# bontor_mbed_lowpan_rev_b.net
KiCad netlist of a schematic drawn in EAGLE
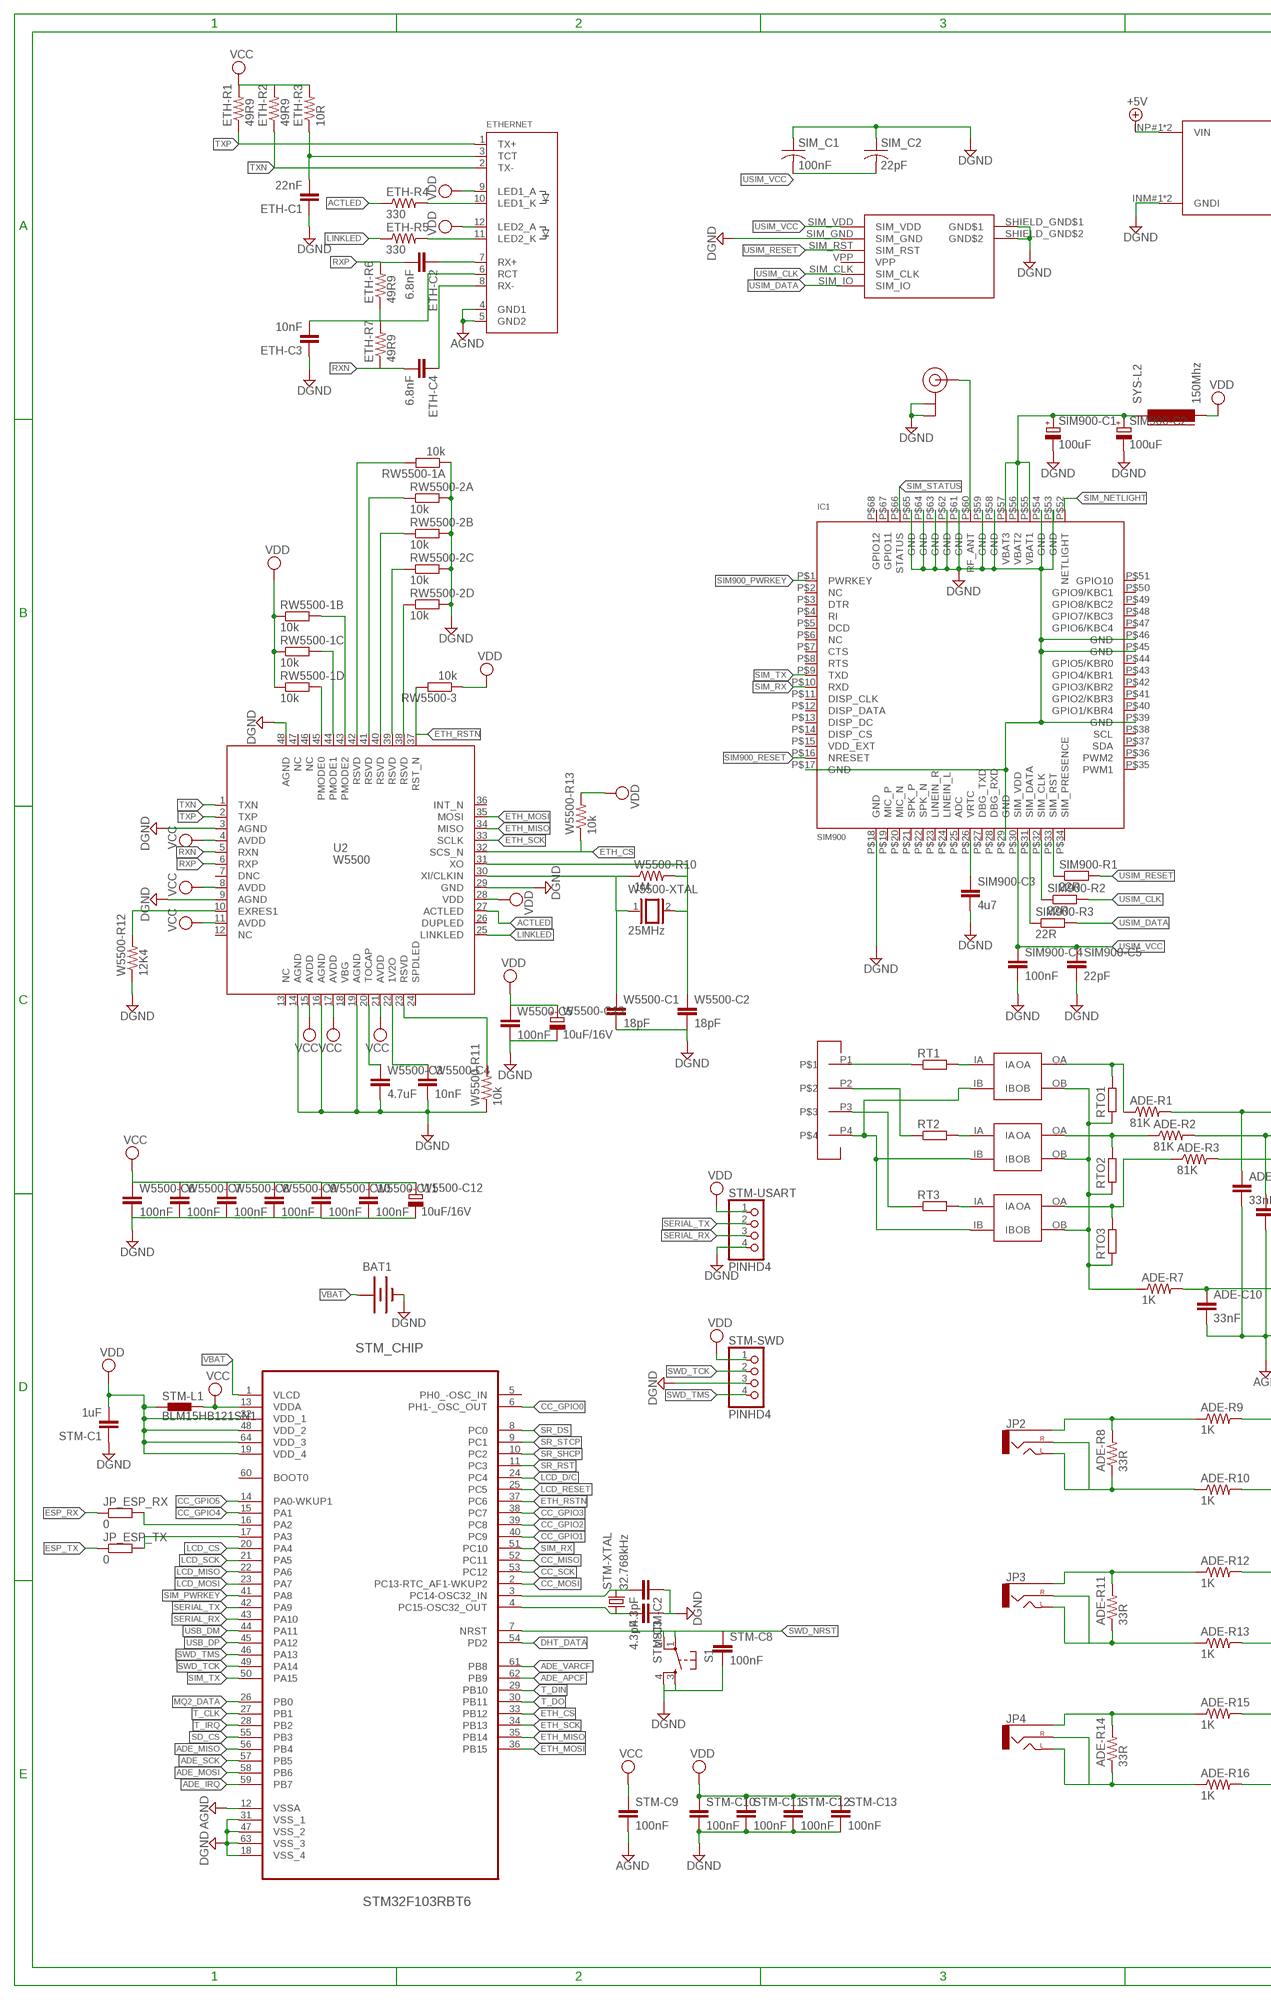
[diagram p0: schematic, sheet 1, part 1 of 2]
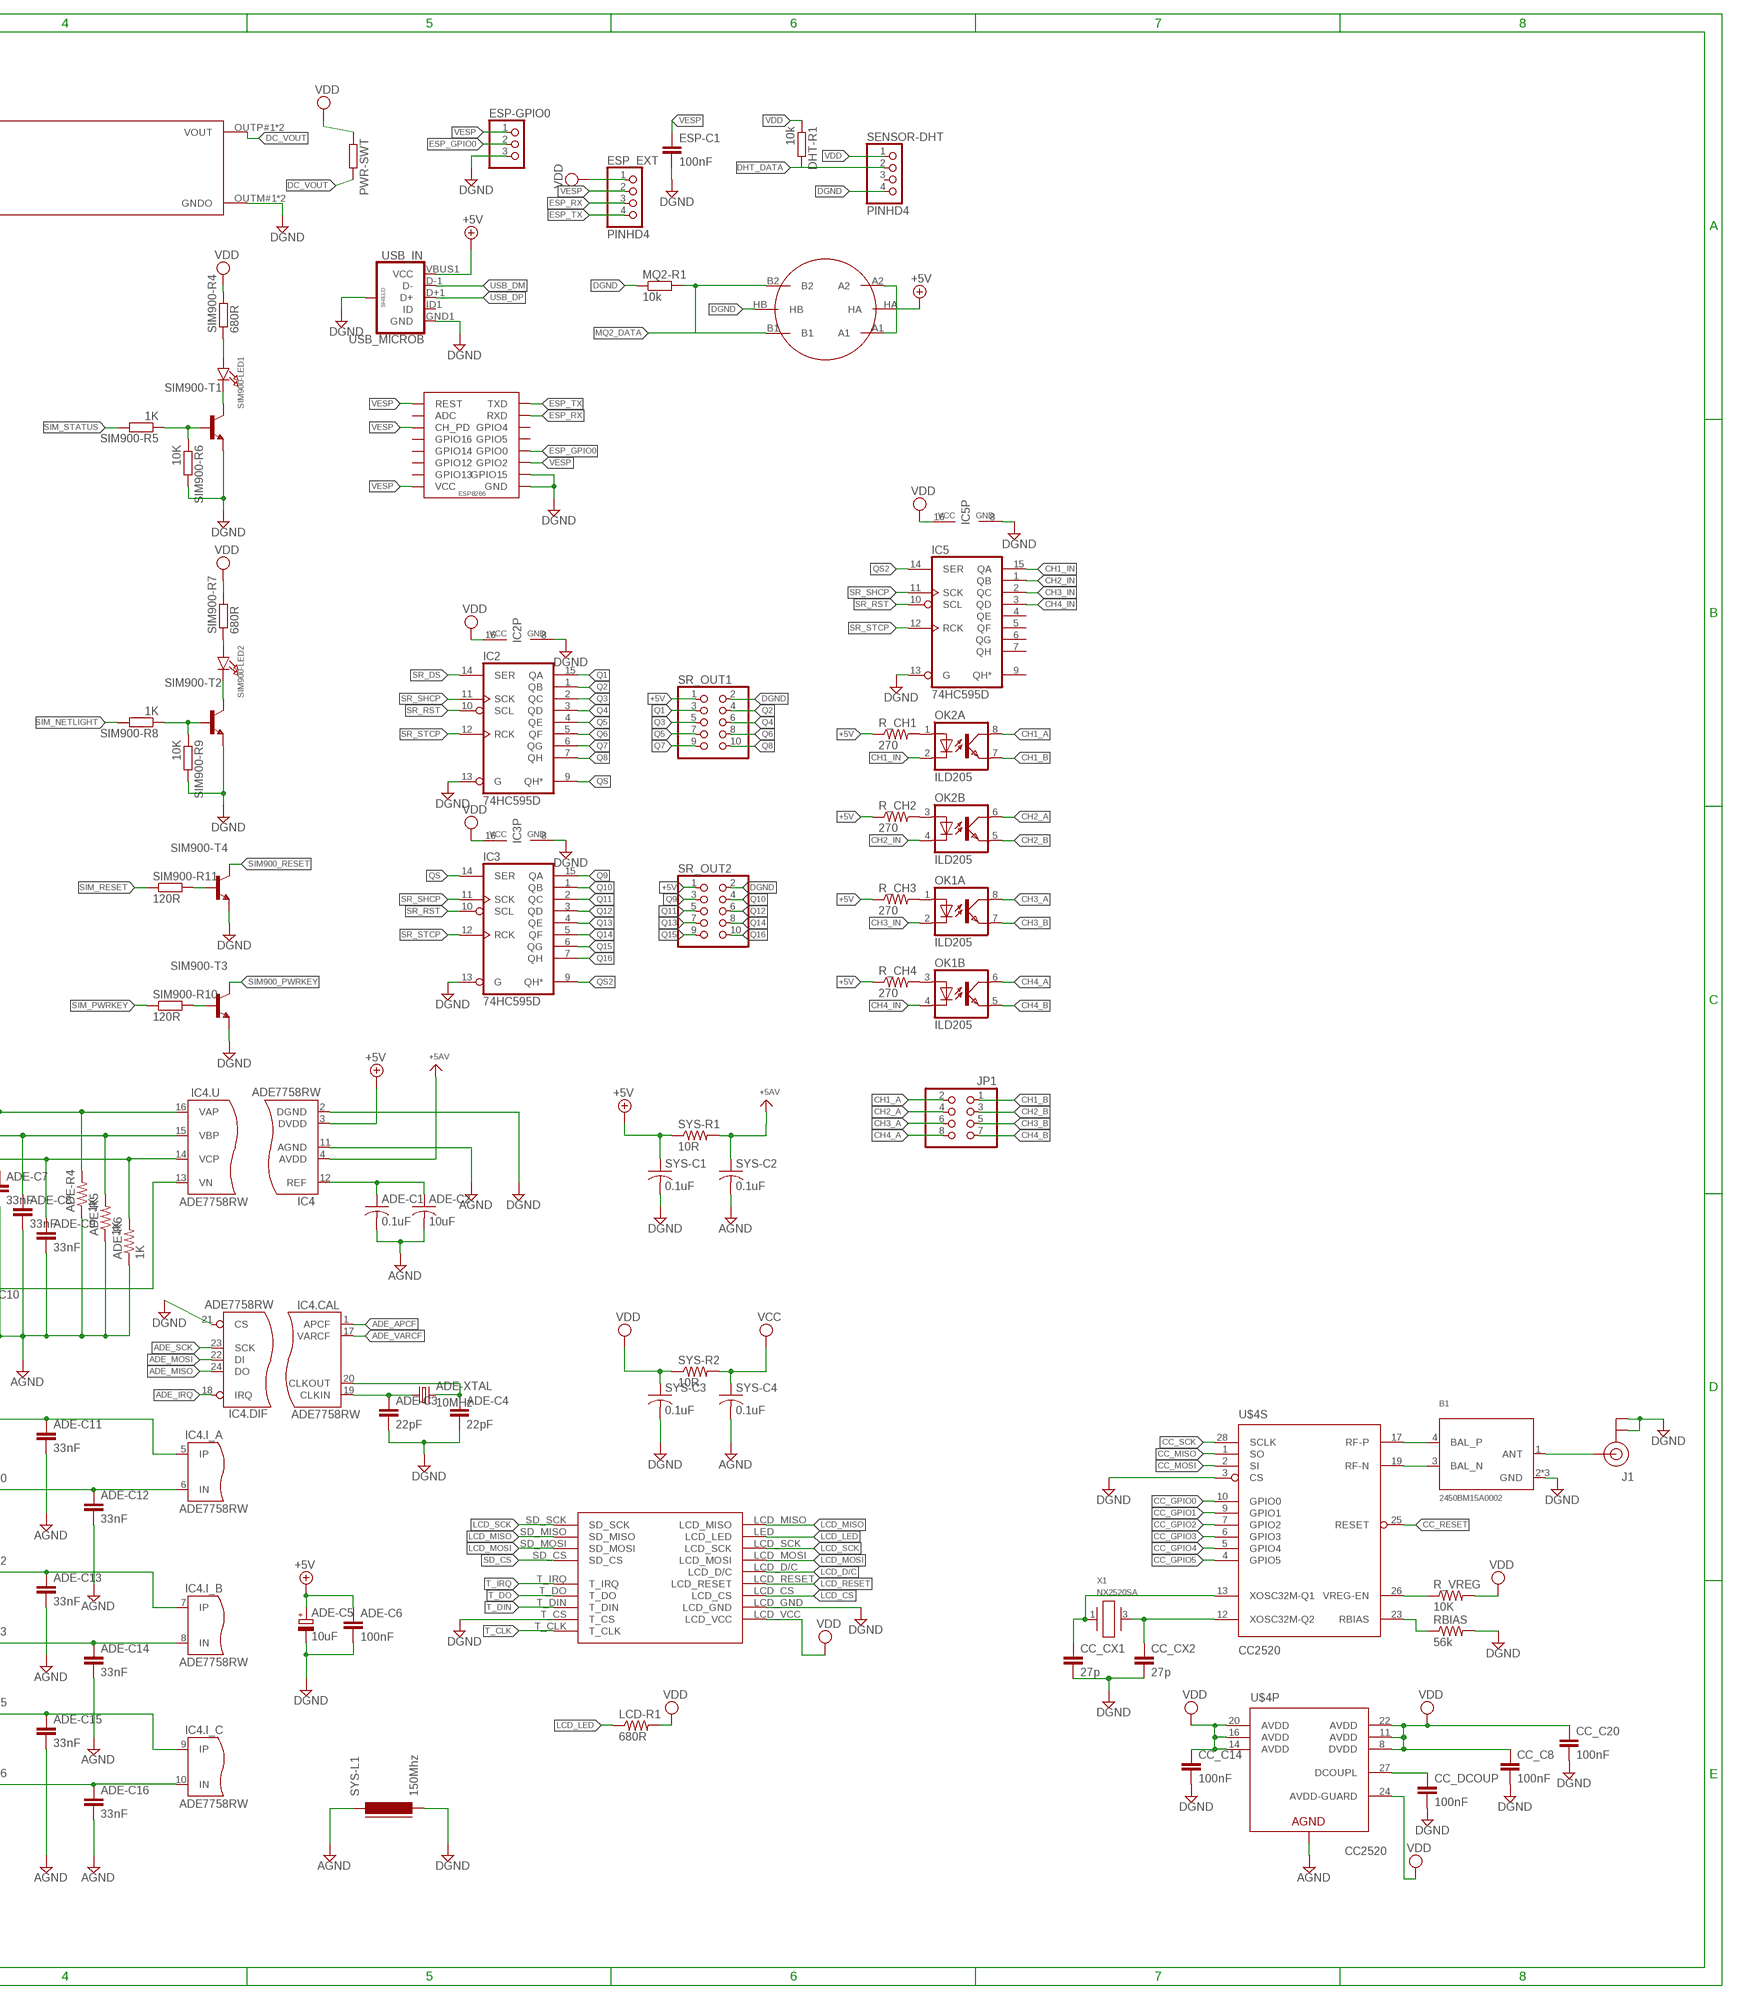
[diagram p1: schematic, sheet 1, part 2 of 2]

(export (version "E")
  (design (tool "Eeschema 10.0.6"))
  (components
    (comp (ref "ADE-C1")
      (value "0.1uF")
      (footprint "eagle-import:C0603@1")
      (libsource (lib "eagle-import") (part "C-USC0603"))
    )
    (comp (ref "ADE-C2")
      (value "10uF")
      (footprint "eagle-import:C0805K")
      (libsource (lib "eagle-import") (part "C-USC0805K"))
    )
    (comp (ref "ADE-C3")
      (value "22pF")
      (footprint "eagle-import:C0603")
      (libsource (lib "eagle-import") (part "C-EUC0603"))
    )
    (comp (ref "ADE-C4")
      (value "22pF")
      (footprint "eagle-import:C0603")
      (libsource (lib "eagle-import") (part "C-EUC0603"))
    )
    (comp (ref "ADE-C5")
      (value "10uF")
      (footprint "eagle-import:153CLV-0605")
      (libsource (lib "eagle-import") (part "CPOL-EU153CLV-0605"))
    )
    (comp (ref "ADE-C6")
      (value "100nF")
      (footprint "eagle-import:C0603")
      (libsource (lib "eagle-import") (part "C-EUC0603"))
    )
    (comp (ref "ADE-C7")
      (value "33nF")
      (footprint "eagle-import:0603-CAP")
      (libsource (lib "eagle-import") (part "CAP0603-CAP"))
    )
    (comp (ref "ADE-C8")
      (value "33nF")
      (footprint "eagle-import:0603-CAP")
      (libsource (lib "eagle-import") (part "CAP0603-CAP"))
    )
    (comp (ref "ADE-C9")
      (value "33nF")
      (footprint "eagle-import:0603-CAP")
      (libsource (lib "eagle-import") (part "CAP0603-CAP"))
    )
    (comp (ref "ADE-C10")
      (value "33nF")
      (footprint "eagle-import:0603-CAP")
      (libsource (lib "eagle-import") (part "CAP0603-CAP"))
    )
    (comp (ref "ADE-C11")
      (value "33nF")
      (footprint "eagle-import:0603-CAP")
      (libsource (lib "eagle-import") (part "CAP0603-CAP"))
    )
    (comp (ref "ADE-C12")
      (value "33nF")
      (footprint "eagle-import:0603-CAP")
      (libsource (lib "eagle-import") (part "CAP0603-CAP"))
    )
    (comp (ref "ADE-C13")
      (value "33nF")
      (footprint "eagle-import:0603-CAP")
      (libsource (lib "eagle-import") (part "CAP0603-CAP"))
    )
    (comp (ref "ADE-C14")
      (value "33nF")
      (footprint "eagle-import:0603-CAP")
      (libsource (lib "eagle-import") (part "CAP0603-CAP"))
    )
    (comp (ref "ADE-C15")
      (value "33nF")
      (footprint "eagle-import:0603-CAP")
      (libsource (lib "eagle-import") (part "CAP0603-CAP"))
    )
    (comp (ref "ADE-C16")
      (value "33nF")
      (footprint "eagle-import:0603-CAP")
      (libsource (lib "eagle-import") (part "CAP0603-CAP"))
    )
    (comp (ref "ADE-R1")
      (value "81K")
      (footprint "eagle-import:0603-RES")
      (libsource (lib "eagle-import") (part "RESISTOR0603-RES"))
    )
    (comp (ref "ADE-R2")
      (value "81K")
      (footprint "eagle-import:0603-RES")
      (libsource (lib "eagle-import") (part "RESISTOR0603-RES"))
    )
    (comp (ref "ADE-R3")
      (value "81K")
      (footprint "eagle-import:0603-RES")
      (libsource (lib "eagle-import") (part "RESISTOR0603-RES"))
    )
    (comp (ref "ADE-R4")
      (value "1K")
      (footprint "eagle-import:0603-RES")
      (libsource (lib "eagle-import") (part "RESISTOR0603-RES"))
    )
    (comp (ref "ADE-R5")
      (value "1K")
      (footprint "eagle-import:0603-RES")
      (libsource (lib "eagle-import") (part "RESISTOR0603-RES"))
    )
    (comp (ref "ADE-R6")
      (value "1K")
      (footprint "eagle-import:0603-RES")
      (libsource (lib "eagle-import") (part "RESISTOR0603-RES"))
    )
    (comp (ref "ADE-R7")
      (value "1K")
      (footprint "eagle-import:0603-RES")
      (libsource (lib "eagle-import") (part "RESISTOR0603-RES"))
    )
    (comp (ref "ADE-R8")
      (value "33R")
      (footprint "eagle-import:0603-RES")
      (libsource (lib "eagle-import") (part "RESISTOR0603-RES"))
    )
    (comp (ref "ADE-R9")
      (value "1K")
      (footprint "eagle-import:0603-RES")
      (libsource (lib "eagle-import") (part "RESISTOR0603-RES"))
    )
    (comp (ref "ADE-R10")
      (value "1K")
      (footprint "eagle-import:0603-RES")
      (libsource (lib "eagle-import") (part "RESISTOR0603-RES"))
    )
    (comp (ref "ADE-R11")
      (value "33R")
      (footprint "eagle-import:0603-RES")
      (libsource (lib "eagle-import") (part "RESISTOR0603-RES"))
    )
    (comp (ref "ADE-R12")
      (value "1K")
      (footprint "eagle-import:0603-RES")
      (libsource (lib "eagle-import") (part "RESISTOR0603-RES"))
    )
    (comp (ref "ADE-R13")
      (value "1K")
      (footprint "eagle-import:0603-RES")
      (libsource (lib "eagle-import") (part "RESISTOR0603-RES"))
    )
    (comp (ref "ADE-R14")
      (value "33R")
      (footprint "eagle-import:0603-RES")
      (libsource (lib "eagle-import") (part "RESISTOR0603-RES"))
    )
    (comp (ref "ADE-R15")
      (value "1K")
      (footprint "eagle-import:0603-RES")
      (libsource (lib "eagle-import") (part "RESISTOR0603-RES"))
    )
    (comp (ref "ADE-R16")
      (value "1K")
      (footprint "eagle-import:0603-RES")
      (libsource (lib "eagle-import") (part "RESISTOR0603-RES"))
    )
    (comp (ref "ADE-XTAL")
      (value "10MHz")
      (footprint "eagle-import:HC49US")
      (libsource (lib "eagle-import") (part "CRYSTALHC49US"))
    )
    (comp (ref "B1")
      (value "2450BM15A0002")
      (footprint "eagle-import:2450BM")
      (libsource (lib "eagle-import") (part "2450BM15A0002"))
    )
    (comp (ref "BAT1")
      (value "BATTERY12MM")
      (footprint "eagle-import:BATTCON_12MM")
      (libsource (lib "eagle-import") (part "BATTERY12MM"))
    )
    (comp (ref "CC_C8")
      (value "100nF")
      (footprint "eagle-import:C0402")
      (libsource (lib "eagle-import") (part "C-EUC0402"))
    )
    (comp (ref "CC_C14")
      (value "100nF")
      (footprint "eagle-import:C0402")
      (libsource (lib "eagle-import") (part "C-EUC0402"))
    )
    (comp (ref "CC_C20")
      (value "100nF")
      (footprint "eagle-import:C0402")
      (libsource (lib "eagle-import") (part "C-EUC0402"))
    )
    (comp (ref "CC_CX1")
      (value "27p")
      (footprint "eagle-import:C0201")
      (libsource (lib "eagle-import") (part "C-EUC0201"))
    )
    (comp (ref "CC_CX2")
      (value "27p")
      (footprint "eagle-import:C0201")
      (libsource (lib "eagle-import") (part "C-EUC0201"))
    )
    (comp (ref "CC_DCOUP")
      (value "100nF")
      (footprint "eagle-import:C0402")
      (libsource (lib "eagle-import") (part "C-EUC0402"))
    )
    (comp (ref "DCDC-3.5V")
      (value "DCDCMODULE_SMALL")
      (footprint "eagle-import:DCDCMODULE-SMALL")
      (libsource (lib "eagle-import") (part "DCDCMODULE_SMALL"))
    )
    (comp (ref "DHT-R1")
      (value "10k")
      (footprint "eagle-import:R0603")
      (libsource (lib "eagle-import") (part "resistor_R-EU_R0603"))
    )
    (comp (ref "ESP-C1")
      (value "100nF")
      (footprint "eagle-import:C0603")
      (libsource (lib "eagle-import") (part "C-EUC0603"))
    )
    (comp (ref "ESP-GPIO0")
      (value "PINHD-1X3")
      (footprint "eagle-import:1X03")
      (libsource (lib "eagle-import") (part "PINHD-1X3"))
    )
    (comp (ref "ESP_EXT")
      (value "PINHD4")
      (footprint "eagle-import:PINHD4")
      (libsource (lib "eagle-import") (part "PINHD4"))
    )
    (comp (ref "ETH-C1")
      (value "22nF")
      (footprint "eagle-import:C0603")
      (libsource (lib "eagle-import") (part "C-EUC0603"))
    )
    (comp (ref "ETH-C2")
      (value "6.8nF")
      (footprint "eagle-import:C0603")
      (libsource (lib "eagle-import") (part "C-EUC0603"))
    )
    (comp (ref "ETH-C3")
      (value "10nF")
      (footprint "eagle-import:C0603")
      (libsource (lib "eagle-import") (part "C-EUC0603"))
    )
    (comp (ref "ETH-C4")
      (value "6.8nF")
      (footprint "eagle-import:C0603")
      (libsource (lib "eagle-import") (part "C-EUC0603"))
    )
    (comp (ref "ETH-R1")
      (value "49R9")
      (footprint "eagle-import:R0603")
      (libsource (lib "eagle-import") (part "R-US_R0603"))
    )
    (comp (ref "ETH-R2")
      (value "49R9")
      (footprint "eagle-import:R0603")
      (libsource (lib "eagle-import") (part "R-US_R0603"))
    )
    (comp (ref "ETH-R3")
      (value "10R")
      (footprint "eagle-import:R0603")
      (libsource (lib "eagle-import") (part "R-US_R0603"))
    )
    (comp (ref "ETH-R4")
      (value "330")
      (footprint "eagle-import:R0603")
      (libsource (lib "eagle-import") (part "R-US_R0603"))
    )
    (comp (ref "ETH-R5")
      (value "330")
      (footprint "eagle-import:R0603")
      (libsource (lib "eagle-import") (part "R-US_R0603"))
    )
    (comp (ref "ETH-R6")
      (value "49R9")
      (footprint "eagle-import:R0603")
      (libsource (lib "eagle-import") (part "R-US_R0603"))
    )
    (comp (ref "ETH-R7")
      (value "49R9")
      (footprint "eagle-import:R0603")
      (libsource (lib "eagle-import") (part "R-US_R0603"))
    )
    (comp (ref "ETHERNET")
      (value "RJ45J0026D21BNL")
      (footprint "eagle-import:RJ45_PULSEJACK")
      (libsource (lib "eagle-import") (part "RJ45J0026D21BNL"))
    )
    (comp (ref "IC1")
      (value "SIM900")
      (footprint "eagle-import:SIM900_SMT")
      (libsource (lib "eagle-import") (part "GSM_SIM900_LITERAL"))
    )
    (comp (ref "IC2")
      (value "74HC595D")
      (footprint "eagle-import:SO16")
      (libsource (lib "eagle-import") (part "74595DHC"))
    )
    (comp (ref "IC3")
      (value "74HC595D")
      (footprint "eagle-import:SO16")
      (libsource (lib "eagle-import") (part "74595DHC"))
    )
    (comp (ref "IC4")
      (value "ADE7758RW")
      (footprint "eagle-import:SOIC24")
      (libsource (lib "eagle-import") (part "ADE7758RW"))
    )
    (comp (ref "IC5")
      (value "74HC595D")
      (footprint "eagle-import:SO16")
      (libsource (lib "eagle-import") (part "74595DHC"))
    )
    (comp (ref "J1")
      (value "U.FL")
      (footprint "eagle-import:U.FL")
      (libsource (lib "eagle-import") (part "SparkFun-Connectors_U.FL"))
    )
    (comp (ref "JP1")
      (value "PINHD-2X4")
      (footprint "eagle-import:2X04")
      (libsource (lib "eagle-import") (part "PINHD-2X4"))
    )
    (comp (ref "JP2")
      (value "AUDIO-JACKSMD2")
      (footprint "eagle-import:AUDIO-JACK-3.5MM-SMD")
      (libsource (lib "eagle-import") (part "AUDIO-JACKSMD2"))
    )
    (comp (ref "JP3")
      (value "AUDIO-JACKSMD2")
      (footprint "eagle-import:AUDIO-JACK-3.5MM-SMD")
      (libsource (lib "eagle-import") (part "AUDIO-JACKSMD2"))
    )
    (comp (ref "JP4")
      (value "AUDIO-JACKSMD2")
      (footprint "eagle-import:AUDIO-JACK-3.5MM-SMD")
      (libsource (lib "eagle-import") (part "AUDIO-JACKSMD2"))
    )
    (comp (ref "JP_ESP_RX")
      (value "0")
      (footprint "eagle-import:R0201")
      (libsource (lib "eagle-import") (part "R-EU_R0201"))
    )
    (comp (ref "JP_ESP_TX")
      (value "0")
      (footprint "eagle-import:R0201")
      (libsource (lib "eagle-import") (part "R-EU_R0201"))
    )
    (comp (ref "LCD-R1")
      (value "680R")
      (footprint "eagle-import:0603-RES")
      (libsource (lib "eagle-import") (part "RESISTOR0603-RES"))
    )
    (comp (ref "MQ2-R1")
      (value "10k")
      (footprint "eagle-import:R0603")
      (libsource (lib "eagle-import") (part "resistor_R-EU_R0603"))
    )
    (comp (ref "OK1")
      (value "ILD205")
      (footprint "eagle-import:SOIC08")
      (fields (field (name "MF") "VISHAY/TELEFUNKEN") (field (name "MPN") "ILD205T"))
      (libsource (lib "eagle-import") (part "ILD205"))
    )
    (comp (ref "OK2")
      (value "ILD205")
      (footprint "eagle-import:SOIC08")
      (fields (field (name "MF") "VISHAY/TELEFUNKEN") (field (name "MPN") "ILD205T"))
      (libsource (lib "eagle-import") (part "ILD205"))
    )
    (comp (ref "PWR-SWT")
      (value "R-EU_R0402")
      (footprint "eagle-import:R0402")
      (libsource (lib "eagle-import") (part "R-EU_R0402"))
    )
    (comp (ref "RBIAS")
      (value "56k")
      (footprint "eagle-import:0402-RES")
      (libsource (lib "eagle-import") (part "RESISTOR0402-RES"))
    )
    (comp (ref "RT1")
      (value "R-EU_0309/V")
      (footprint "eagle-import:0309V")
      (libsource (lib "eagle-import") (part "R-EU_0309/V"))
    )
    (comp (ref "RT2")
      (value "R-EU_0309/V")
      (footprint "eagle-import:0309V")
      (libsource (lib "eagle-import") (part "R-EU_0309/V"))
    )
    (comp (ref "RT3")
      (value "R-EU_0309/V")
      (footprint "eagle-import:0309V")
      (libsource (lib "eagle-import") (part "R-EU_0309/V"))
    )
    (comp (ref "RTO1")
      (value "R-EU_0309/12")
      (footprint "eagle-import:0309_12")
      (libsource (lib "eagle-import") (part "R-EU_0309/12"))
    )
    (comp (ref "RTO2")
      (value "R-EU_0309/12")
      (footprint "eagle-import:0309_12")
      (libsource (lib "eagle-import") (part "R-EU_0309/12"))
    )
    (comp (ref "RTO3")
      (value "R-EU_0309/12")
      (footprint "eagle-import:0309_12")
      (libsource (lib "eagle-import") (part "R-EU_0309/12"))
    )
    (comp (ref "RW5500-1")
      (value "10k")
      (footprint "eagle-import:RN8P-4R-CRA06S")
      (libsource (lib "eagle-import") (part "RESISTOR_ARRAY_4"))
    )
    (comp (ref "RW5500-2")
      (value "10k")
      (footprint "eagle-import:RN8P-4R-CRA06S")
      (libsource (lib "eagle-import") (part "RESISTOR_ARRAY_4"))
    )
    (comp (ref "RW5500-3")
      (value "10k")
      (footprint "eagle-import:R0603")
      (libsource (lib "eagle-import") (part "R-EU_R0603"))
    )
    (comp (ref "R_CH1")
      (value "270")
      (footprint "eagle-import:0603-RES")
      (libsource (lib "eagle-import") (part "RESISTOR0603-RES"))
    )
    (comp (ref "R_CH2")
      (value "270")
      (footprint "eagle-import:0603-RES")
      (libsource (lib "eagle-import") (part "RESISTOR0603-RES"))
    )
    (comp (ref "R_CH3")
      (value "270")
      (footprint "eagle-import:0603-RES")
      (libsource (lib "eagle-import") (part "RESISTOR0603-RES"))
    )
    (comp (ref "R_CH4")
      (value "270")
      (footprint "eagle-import:0603-RES")
      (libsource (lib "eagle-import") (part "RESISTOR0603-RES"))
    )
    (comp (ref "R_VREG")
      (value "10K")
      (footprint "eagle-import:0402-RES")
      (libsource (lib "eagle-import") (part "RESISTOR0402-RES"))
    )
    (comp (ref "S1")
      (value "TAC_SWITCHSMD")
      (footprint "eagle-import:TACTILE-SWITCH-SMD")
      (libsource (lib "eagle-import") (part "TAC_SWITCHSMD"))
    )
    (comp (ref "SENSOR-DHT")
      (value "PINHD4")
      (footprint "eagle-import:PINHD4")
      (libsource (lib "eagle-import") (part "PINHD4"))
    )
    (comp (ref "SENSOR-MQ2")
      (value "METHANE_SENSOR")
      (footprint "eagle-import:MQ-3")
      (libsource (lib "eagle-import") (part "METHANE_SENSOR"))
    )
    (comp (ref "SIM900-C1")
      (value "100uF")
      (footprint "eagle-import:153CLV-0605")
      (libsource (lib "eagle-import") (part "CPOL-EU153CLV-0605"))
    )
    (comp (ref "SIM900-C2")
      (value "100uF")
      (footprint "eagle-import:153CLV-0605")
      (libsource (lib "eagle-import") (part "CPOL-EU153CLV-0605"))
    )
    (comp (ref "SIM900-C3")
      (value "4u7")
      (footprint "eagle-import:C0603")
      (libsource (lib "eagle-import") (part "C-EUC0603"))
    )
    (comp (ref "SIM900-C4")
      (value "100nF")
      (footprint "eagle-import:C0603")
      (libsource (lib "eagle-import") (part "C-EUC0603"))
    )
    (comp (ref "SIM900-C5")
      (value "22pF")
      (footprint "eagle-import:C0603")
      (libsource (lib "eagle-import") (part "C-EUC0603"))
    )
    (comp (ref "SIM900-LED1")
      (value "LED0805_NOOUTLINE")
      (footprint "eagle-import:CHIPLED_0805_NOOUTLINE")
      (libsource (lib "eagle-import") (part "LED0805_NOOUTLINE"))
    )
    (comp (ref "SIM900-LED2")
      (value "LED0805_NOOUTLINE")
      (footprint "eagle-import:CHIPLED_0805_NOOUTLINE")
      (libsource (lib "eagle-import") (part "LED0805_NOOUTLINE"))
    )
    (comp (ref "SIM900-R1")
      (value "22R")
      (footprint "eagle-import:R0603")
      (libsource (lib "eagle-import") (part "R-EU_R0603"))
    )
    (comp (ref "SIM900-R2")
      (value "22R")
      (footprint "eagle-import:R0603")
      (libsource (lib "eagle-import") (part "R-EU_R0603"))
    )
    (comp (ref "SIM900-R3")
      (value "22R")
      (footprint "eagle-import:R0603")
      (libsource (lib "eagle-import") (part "R-EU_R0603"))
    )
    (comp (ref "SIM900-R4")
      (value "680R")
      (footprint "eagle-import:R0603")
      (libsource (lib "eagle-import") (part "R-EU_R0603"))
    )
    (comp (ref "SIM900-R5")
      (value "1K")
      (footprint "eagle-import:R0603")
      (libsource (lib "eagle-import") (part "R-EU_R0603"))
    )
    (comp (ref "SIM900-R6")
      (value "10K")
      (footprint "eagle-import:R0603")
      (libsource (lib "eagle-import") (part "R-EU_R0603"))
    )
    (comp (ref "SIM900-R7")
      (value "680R")
      (footprint "eagle-import:R0603")
      (libsource (lib "eagle-import") (part "R-EU_R0603"))
    )
    (comp (ref "SIM900-R8")
      (value "1K")
      (footprint "eagle-import:R0603")
      (libsource (lib "eagle-import") (part "R-EU_R0603"))
    )
    (comp (ref "SIM900-R9")
      (value "10K")
      (footprint "eagle-import:R0603")
      (libsource (lib "eagle-import") (part "R-EU_R0603"))
    )
    (comp (ref "SIM900-R10")
      (value "120R")
      (footprint "eagle-import:R0603")
      (libsource (lib "eagle-import") (part "resistor_R-EU_R0603"))
    )
    (comp (ref "SIM900-R11")
      (value "120R")
      (footprint "eagle-import:R0603")
      (libsource (lib "eagle-import") (part "resistor_R-EU_R0603"))
    )
    (comp (ref "SIM900-T1")
      (value "MMBT2222ALT1-NPN-SOT23-BEC")
      (footprint "eagle-import:SOT23-BEC")
      (libsource (lib "eagle-import") (part "-NPN-SOT23-BECMMBT2222ALT1"))
    )
    (comp (ref "SIM900-T2")
      (value "MMBT2222ALT1-NPN-SOT23-BEC")
      (footprint "eagle-import:SOT23-BEC")
      (libsource (lib "eagle-import") (part "-NPN-SOT23-BECMMBT2222ALT1"))
    )
    (comp (ref "SIM900-T3")
      (value "MMBT2222ALT1-NPN-SOT23-BEC")
      (footprint "eagle-import:SOT23-BEC")
      (libsource (lib "eagle-import") (part "transistor-neu-to92_-NPN-SOT23-BECMMBT2222ALT1"))
    )
    (comp (ref "SIM900-T4")
      (value "MMBT2222ALT1-NPN-SOT23-BEC")
      (footprint "eagle-import:SOT23-BEC")
      (libsource (lib "eagle-import") (part "transistor-neu-to92_-NPN-SOT23-BECMMBT2222ALT1"))
    )
    (comp (ref "SIM_C1")
      (value "100nF")
      (footprint "eagle-import:C0603K")
      (libsource (lib "eagle-import") (part "C-USC0603K"))
    )
    (comp (ref "SIM_C2")
      (value "22pF")
      (footprint "eagle-import:C0603K")
      (libsource (lib "eagle-import") (part "C-USC0603K"))
    )
    (comp (ref "SR_OUT1")
      (value "PINHD-2X5/90")
      (footprint "eagle-import:2X05_90")
      (libsource (lib "eagle-import") (part "PINHD-2X5/90"))
    )
    (comp (ref "SR_OUT2")
      (value "PINHD-2X5/90")
      (footprint "eagle-import:2X05_90")
      (libsource (lib "eagle-import") (part "PINHD-2X5/90"))
    )
    (comp (ref "STM-C1")
      (value "1uF")
      (footprint "eagle-import:C0603")
      (libsource (lib "eagle-import") (part "C-EUC0603"))
    )
    (comp (ref "STM-C2")
      (value "4.3pF")
      (footprint "eagle-import:C0603")
      (libsource (lib "eagle-import") (part "C-EUC0603"))
    )
    (comp (ref "STM-C3")
      (value "4.3pF")
      (footprint "eagle-import:C0603")
      (libsource (lib "eagle-import") (part "C-EUC0603"))
    )
    (comp (ref "STM-C8")
      (value "100nF")
      (footprint "eagle-import:C0603")
      (libsource (lib "eagle-import") (part "C-EUC0603"))
    )
    (comp (ref "STM-C9")
      (value "100nF")
      (footprint "eagle-import:C0603")
      (libsource (lib "eagle-import") (part "C-EUC0603"))
    )
    (comp (ref "STM-C10")
      (value "100nF")
      (footprint "eagle-import:C0603")
      (libsource (lib "eagle-import") (part "C-EUC0603"))
    )
    (comp (ref "STM-C11")
      (value "100nF")
      (footprint "eagle-import:C0603")
      (libsource (lib "eagle-import") (part "C-EUC0603"))
    )
    (comp (ref "STM-C12")
      (value "100nF")
      (footprint "eagle-import:C0603")
      (libsource (lib "eagle-import") (part "C-EUC0603"))
    )
    (comp (ref "STM-C13")
      (value "100nF")
      (footprint "eagle-import:C0603")
      (libsource (lib "eagle-import") (part "C-EUC0603"))
    )
    (comp (ref "STM-L1")
      (value "BLM15HB121SN1")
      (footprint "eagle-import:0402")
      (libsource (lib "eagle-import") (part "BLM15HB121SN1"))
    )
    (comp (ref "STM-SWD")
      (value "PINHD4")
      (footprint "eagle-import:PINHD4")
      (libsource (lib "eagle-import") (part "PINHD4"))
    )
    (comp (ref "STM-USART")
      (value "PINHD4")
      (footprint "eagle-import:PINHD4")
      (libsource (lib "eagle-import") (part "PINHD4"))
    )
    (comp (ref "STM-XTAL")
      (value "32.768kHz")
      (footprint "eagle-import:TC26H")
      (libsource (lib "eagle-import") (part "CRYSTALTC26H"))
    )
    (comp (ref "STM_CHIP")
      (value "STM32F103RBT6")
      (footprint "eagle-import:QFP50P1200X1200X160-64N")
      (fields (field (name "MPN") "STM32L152RBT6"))
      (libsource (lib "eagle-import") (part "STM32L152RBT6"))
    )
    (comp (ref "SYS-C1")
      (value "0.1uF")
      (footprint "eagle-import:C0603@1")
      (libsource (lib "eagle-import") (part "C-USC0603"))
    )
    (comp (ref "SYS-C2")
      (value "0.1uF")
      (footprint "eagle-import:C0603@1")
      (libsource (lib "eagle-import") (part "C-USC0603"))
    )
    (comp (ref "SYS-C3")
      (value "0.1uF")
      (footprint "eagle-import:C0603@1")
      (libsource (lib "eagle-import") (part "C-USC0603"))
    )
    (comp (ref "SYS-C4")
      (value "0.1uF")
      (footprint "eagle-import:C0603@1")
      (libsource (lib "eagle-import") (part "C-USC0603"))
    )
    (comp (ref "SYS-L1")
      (value "150Mhz")
      (footprint "eagle-import:FB805")
      (libsource (lib "eagle-import") (part "FERRITE-0805"))
    )
    (comp (ref "SYS-L2")
      (value "150Mhz")
      (footprint "eagle-import:FB805")
      (libsource (lib "eagle-import") (part "FERRITE-0805"))
    )
    (comp (ref "SYS-R1")
      (value "10R")
      (footprint "eagle-import:0603-RES")
      (libsource (lib "eagle-import") (part "RESISTOR0603-RES"))
    )
    (comp (ref "SYS-R2")
      (value "10R")
      (footprint "eagle-import:0603-RES")
      (libsource (lib "eagle-import") (part "RESISTOR0603-RES"))
    )
    (comp (ref "U$4")
      (value "CC2520")
      (footprint "eagle-import:QFN50P500X500X100-29N")
      (libsource (lib "eagle-import") (part "CC2520"))
    )
    (comp (ref "U$5")
      (value "ESP8266WI12")
      (footprint "eagle-import:WI12")
      (libsource (lib "eagle-import") (part "ESP8266WI12"))
    )
    (comp (ref "U$7")
      (value "U.FL")
      (footprint "eagle-import:U.FL")
      (libsource (lib "eagle-import") (part "U.FL"))
    )
    (comp (ref "U$8")
      (value "SIM_HOLDER")
      (footprint "eagle-import:SIMHOLDER-PUSHPUSH")
      (libsource (lib "eagle-import") (part "SIM_HOLDER"))
    )
    (comp (ref "U$9")
      (value "TRANSFORMER")
      (footprint "eagle-import:TV16")
      (libsource (lib "eagle-import") (part "TRANSFORMER"))
    )
    (comp (ref "U$10")
      (value "TRANSFORMER")
      (footprint "eagle-import:TV16")
      (libsource (lib "eagle-import") (part "TRANSFORMER"))
    )
    (comp (ref "U$11")
      (value "TRANSFORMER")
      (footprint "eagle-import:TV16")
      (libsource (lib "eagle-import") (part "TRANSFORMER"))
    )
    (comp (ref "U$12")
      (value "TERMINAL_BLOCK")
      (footprint "eagle-import:TERMINAL-RIGHT-ANGLE")
      (libsource (lib "eagle-import") (part "TERMINAL_BLOCK"))
    )
    (comp (ref "U$13")
      (value "LCD_2.4")
      (footprint "eagle-import:LCD_TOUCH_2-4")
      (libsource (lib "eagle-import") (part "LCD_2.4"))
    )
    (comp (ref "U2")
      (value "W5500")
      (footprint "eagle-import:W5500")
      (libsource (lib "eagle-import") (part "W5500"))
    )
    (comp (ref "USB_IN")
      (value "USB_MICROB")
      (footprint "eagle-import:USB-B-MICRO-SMD_V03")
      (libsource (lib "eagle-import") (part "USB_MICROB_PLUGCONN-11752"))
    )
    (comp (ref "W5500-C1")
      (value "18pF")
      (footprint "eagle-import:C0603")
      (libsource (lib "eagle-import") (part "C-EUC0603"))
    )
    (comp (ref "W5500-C2")
      (value "18pF")
      (footprint "eagle-import:C0603")
      (libsource (lib "eagle-import") (part "C-EUC0603"))
    )
    (comp (ref "W5500-C3")
      (value "4.7uF")
      (footprint "eagle-import:C0603")
      (libsource (lib "eagle-import") (part "C-EUC0603"))
    )
    (comp (ref "W5500-C4")
      (value "10nF")
      (footprint "eagle-import:C0603")
      (libsource (lib "eagle-import") (part "C-EUC0603"))
    )
    (comp (ref "W5500-C5")
      (value "100nF")
      (footprint "eagle-import:C0603")
      (libsource (lib "eagle-import") (part "C-EUC0603"))
    )
    (comp (ref "W5500-C6")
      (value "100nF")
      (footprint "eagle-import:C0603")
      (libsource (lib "eagle-import") (part "C-EUC0603"))
    )
    (comp (ref "W5500-C7")
      (value "100nF")
      (footprint "eagle-import:C0603")
      (libsource (lib "eagle-import") (part "C-EUC0603"))
    )
    (comp (ref "W5500-C8")
      (value "100nF")
      (footprint "eagle-import:C0603")
      (libsource (lib "eagle-import") (part "C-EUC0603"))
    )
    (comp (ref "W5500-C9")
      (value "100nF")
      (footprint "eagle-import:C0603")
      (libsource (lib "eagle-import") (part "C-EUC0603"))
    )
    (comp (ref "W5500-C10")
      (value "100nF")
      (footprint "eagle-import:C0603")
      (libsource (lib "eagle-import") (part "C-EUC0603"))
    )
    (comp (ref "W5500-C11")
      (value "100nF")
      (footprint "eagle-import:C0603")
      (libsource (lib "eagle-import") (part "C-EUC0603"))
    )
    (comp (ref "W5500-C12")
      (value "10uF/16V")
      (footprint "eagle-import:153CLV-0605")
      (libsource (lib "eagle-import") (part "CPOL-EU153CLV-0605"))
    )
    (comp (ref "W5500-C13")
      (value "10uF/16V")
      (footprint "eagle-import:153CLV-0605")
      (libsource (lib "eagle-import") (part "CPOL-EU153CLV-0605"))
    )
    (comp (ref "W5500-R10")
      (value "1M")
      (footprint "eagle-import:R0603")
      (libsource (lib "eagle-import") (part "R-US_R0603"))
    )
    (comp (ref "W5500-R11")
      (value "10k")
      (footprint "eagle-import:R0603")
      (libsource (lib "eagle-import") (part "R-US_R0603"))
    )
    (comp (ref "W5500-R12")
      (value "12K4")
      (footprint "eagle-import:R0805")
      (libsource (lib "eagle-import") (part "R-US_R0805"))
    )
    (comp (ref "W5500-R13")
      (value "10k")
      (footprint "eagle-import:R0603")
      (libsource (lib "eagle-import") (part "R-US_R0603"))
    )
    (comp (ref "W5500-XTAL")
      (value "25MHz")
      (footprint "eagle-import:QS")
      (libsource (lib "eagle-import") (part "XTAL/S"))
    )
    (comp (ref "X1")
      (value "NX2520SA")
      (footprint "eagle-import:NX2520SA")
      (libsource (lib "eagle-import") (part "NX2520SA"))
    )
  )
  (nets
    (net (code "1") (name "+5AV") (class "Default")
      (node (ref "IC4") (pin "4") (pinfunction "AVDD_4") (pintype "power_in"))
      (node (ref "SYS-C2") (pin "1") (pinfunction "1_1") (pintype "passive"))
      (node (ref "SYS-R1") (pin "2") (pinfunction "2_2") (pintype "passive"))
    )
    (net (code "2") (name "+5V") (class "Default")
      (node (ref "ADE-C5") (pin "+") (pinfunction "+_+") (pintype "passive"))
      (node (ref "ADE-C6") (pin "1") (pinfunction "1_1") (pintype "passive"))
      (node (ref "DCDC-3.5V") (pin "INP#1") (pinfunction "VIN_INP#1") (pintype "bidirectional"))
      (node (ref "DCDC-3.5V") (pin "INP#2") (pinfunction "VIN_INP#2") (pintype "bidirectional"))
      (node (ref "IC4") (pin "3") (pinfunction "DVDD_3") (pintype "power_in"))
      (node (ref "R_CH1") (pin "1") (pinfunction "1_1") (pintype "passive"))
      (node (ref "R_CH2") (pin "1") (pinfunction "1_1") (pintype "passive"))
      (node (ref "R_CH3") (pin "1") (pinfunction "1_1") (pintype "passive"))
      (node (ref "R_CH4") (pin "1") (pinfunction "1_1") (pintype "passive"))
      (node (ref "SENSOR-MQ2") (pin "A1") (pinfunction "A1_A1") (pintype "bidirectional"))
      (node (ref "SENSOR-MQ2") (pin "A2") (pinfunction "A2_A2") (pintype "bidirectional"))
      (node (ref "SENSOR-MQ2") (pin "HA") (pinfunction "HA_HA") (pintype "bidirectional"))
      (node (ref "SR_OUT1") (pin "1") (pinfunction "1_1") (pintype "passive"))
      (node (ref "SR_OUT2") (pin "1") (pinfunction "1_1") (pintype "passive"))
      (node (ref "SYS-C1") (pin "1") (pinfunction "1_1") (pintype "passive"))
      (node (ref "SYS-R1") (pin "1") (pinfunction "1_1") (pintype "passive"))
      (node (ref "USB_IN") (pin "VBUS1") (pinfunction "VCC_VBUS1") (pintype "bidirectional"))
    )
    (net (code "3") (name "/GPIO11") (class "Default")
      (node (ref "IC1") (pin "P$67") (pinfunction "GPIO11_P$67") (pintype "power_in"))
    )
    (net (code "4") (name "/GPIO12") (class "Default")
      (node (ref "IC1") (pin "P$68") (pinfunction "GPIO12_P$68") (pintype "power_in"))
    )
    (net (code "5") (name "ACTLED") (class "Default")
      (node (ref "ETH-R4") (pin "1") (pinfunction "1_1") (pintype "passive"))
      (node (ref "U2") (pin "27") (pinfunction "ACTLED_27") (pintype "passive"))
    )
    (net (code "6") (name "ADE_APCF") (class "Default")
      (node (ref "IC4") (pin "1") (pinfunction "APCF_1") (pintype "output"))
      (node (ref "STM_CHIP") (pin "62") (pinfunction "PB9_62") (pintype "bidirectional"))
    )
    (net (code "7") (name "ADE_IRQ") (class "Default")
      (node (ref "IC4") (pin "18") (pinfunction "IRQ_18") (pintype "output"))
      (node (ref "STM_CHIP") (pin "59") (pinfunction "PB7_59") (pintype "bidirectional"))
    )
    (net (code "8") (name "ADE_MISO") (class "Default")
      (node (ref "IC4") (pin "24") (pinfunction "DO_24") (pintype "output"))
      (node (ref "STM_CHIP") (pin "56") (pinfunction "PB4_56") (pintype "bidirectional"))
    )
    (net (code "9") (name "ADE_MOSI") (class "Default")
      (node (ref "IC4") (pin "22") (pinfunction "DI_22") (pintype "input"))
      (node (ref "STM_CHIP") (pin "58") (pinfunction "PB6_58") (pintype "bidirectional"))
    )
    (net (code "10") (name "ADE_SCK") (class "Default")
      (node (ref "IC4") (pin "23") (pinfunction "SCK_23") (pintype "input"))
      (node (ref "STM_CHIP") (pin "57") (pinfunction "PB5_57") (pintype "bidirectional"))
    )
    (net (code "11") (name "ADE_VARCF") (class "Default")
      (node (ref "IC4") (pin "17") (pinfunction "VARCF_17") (pintype "output"))
      (node (ref "STM_CHIP") (pin "61") (pinfunction "PB8_61") (pintype "bidirectional"))
    )
    (net (code "12") (name "AGND") (class "Default")
      (node (ref "ADE-C1") (pin "2") (pinfunction "2_2") (pintype "passive"))
      (node (ref "ADE-C10") (pin "2") (pinfunction "2_2") (pintype "passive"))
      (node (ref "ADE-C11") (pin "2") (pinfunction "2_2") (pintype "passive"))
      (node (ref "ADE-C12") (pin "2") (pinfunction "2_2") (pintype "passive"))
      (node (ref "ADE-C13") (pin "2") (pinfunction "2_2") (pintype "passive"))
      (node (ref "ADE-C14") (pin "2") (pinfunction "2_2") (pintype "passive"))
      (node (ref "ADE-C15") (pin "2") (pinfunction "2_2") (pintype "passive"))
      (node (ref "ADE-C16") (pin "2") (pinfunction "2_2") (pintype "passive"))
      (node (ref "ADE-C2") (pin "2") (pinfunction "2_2") (pintype "passive"))
      (node (ref "ADE-C7") (pin "2") (pinfunction "2_2") (pintype "passive"))
      (node (ref "ADE-C8") (pin "2") (pinfunction "2_2") (pintype "passive"))
      (node (ref "ADE-C9") (pin "2") (pinfunction "2_2") (pintype "passive"))
      (node (ref "ADE-R4") (pin "1") (pinfunction "1_1") (pintype "passive"))
      (node (ref "ADE-R5") (pin "1") (pinfunction "1_1") (pintype "passive"))
      (node (ref "ADE-R6") (pin "1") (pinfunction "1_1") (pintype "passive"))
      (node (ref "ETHERNET") (pin "4") (pinfunction "GND1_4") (pintype "bidirectional"))
      (node (ref "ETHERNET") (pin "5") (pinfunction "GND2_5") (pintype "bidirectional"))
      (node (ref "IC4") (pin "11") (pinfunction "AGND_11") (pintype "power_in"))
      (node (ref "STM-C9") (pin "2") (pinfunction "2_2") (pintype "passive"))
      (node (ref "STM_CHIP") (pin "12") (pinfunction "VSSA_12") (pintype "power_in"))
      (node (ref "SYS-C2") (pin "2") (pinfunction "2_2") (pintype "passive"))
      (node (ref "SYS-C4") (pin "2") (pinfunction "2_2") (pintype "passive"))
      (node (ref "SYS-L1") (pin "1") (pinfunction "1_1") (pintype "passive"))
      (node (ref "U$4") (pin "29") (pinfunction "AGND_29") (pintype "power_in"))
    )
    (net (code "13") (name "CC_GPIO0") (class "Default")
      (node (ref "STM_CHIP") (pin "6") (pinfunction "PH1-_OSC_OUT_6") (pintype "bidirectional"))
      (node (ref "U$4") (pin "10") (pinfunction "GPIO0_10") (pintype "output"))
    )
    (net (code "14") (name "CC_GPIO1") (class "Default")
      (node (ref "STM_CHIP") (pin "40") (pinfunction "PC9_40") (pintype "bidirectional"))
      (node (ref "U$4") (pin "9") (pinfunction "GPIO1_9") (pintype "output"))
    )
    (net (code "15") (name "CC_GPIO2") (class "Default")
      (node (ref "STM_CHIP") (pin "39") (pinfunction "PC8_39") (pintype "bidirectional"))
      (node (ref "U$4") (pin "7") (pinfunction "GPIO2_7") (pintype "bidirectional"))
    )
    (net (code "16") (name "CC_GPIO3") (class "Default")
      (node (ref "STM_CHIP") (pin "38") (pinfunction "PC7_38") (pintype "bidirectional"))
      (node (ref "U$4") (pin "6") (pinfunction "GPIO3_6") (pintype "bidirectional"))
    )
    (net (code "17") (name "CC_GPIO4") (class "Default")
      (node (ref "STM_CHIP") (pin "15") (pinfunction "PA1_15") (pintype "bidirectional"))
      (node (ref "U$4") (pin "5") (pinfunction "GPIO4_5") (pintype "bidirectional"))
    )
    (net (code "18") (name "CC_GPIO5") (class "Default")
      (node (ref "STM_CHIP") (pin "14") (pinfunction "PA0-WKUP1_14") (pintype "bidirectional"))
      (node (ref "U$4") (pin "4") (pinfunction "GPIO5_4") (pintype "bidirectional"))
    )
    (net (code "19") (name "CC_MISO") (class "Default")
      (node (ref "STM_CHIP") (pin "52") (pinfunction "PC11_52") (pintype "bidirectional"))
      (node (ref "U$4") (pin "1") (pinfunction "SO_1") (pintype "output"))
    )
    (net (code "20") (name "CC_MOSI") (class "Default")
      (node (ref "STM_CHIP") (pin "2") (pinfunction "PC13-RTC_AF1-WKUP2_2") (pintype "bidirectional"))
      (node (ref "U$4") (pin "2") (pinfunction "SI_2") (pintype "input"))
    )
    (net (code "21") (name "CC_RESET") (class "Default")
      (node (ref "U$4") (pin "25") (pinfunction "RESET_25") (pintype "input"))
    )
    (net (code "22") (name "CC_SCK") (class "Default")
      (node (ref "STM_CHIP") (pin "53") (pinfunction "PC12_53") (pintype "bidirectional"))
      (node (ref "U$4") (pin "28") (pinfunction "SCLK_28") (pintype "input"))
    )
    (net (code "23") (name "CH1_A") (class "Default")
      (node (ref "JP1") (pin "2") (pinfunction "2_2") (pintype "passive"))
      (node (ref "OK2") (pin "8") (pinfunction "COL_8") (pintype "passive"))
    )
    (net (code "24") (name "CH1_B") (class "Default")
      (node (ref "JP1") (pin "1") (pinfunction "1_1") (pintype "passive"))
      (node (ref "OK2") (pin "7") (pinfunction "EMIT_7") (pintype "passive"))
    )
    (net (code "25") (name "CH1_IN") (class "Default")
      (node (ref "IC5") (pin "15") (pinfunction "QA_15") (pintype "tri_state"))
      (node (ref "OK2") (pin "2") (pinfunction "C_2") (pintype "passive"))
    )
    (net (code "26") (name "CH2_A") (class "Default")
      (node (ref "JP1") (pin "4") (pinfunction "4_4") (pintype "passive"))
      (node (ref "OK2") (pin "6") (pinfunction "COL_6") (pintype "passive"))
    )
    (net (code "27") (name "CH2_B") (class "Default")
      (node (ref "JP1") (pin "3") (pinfunction "3_3") (pintype "passive"))
      (node (ref "OK2") (pin "5") (pinfunction "EMIT_5") (pintype "passive"))
    )
    (net (code "28") (name "CH2_IN") (class "Default")
      (node (ref "IC5") (pin "1") (pinfunction "QB_1") (pintype "tri_state"))
      (node (ref "OK2") (pin "4") (pinfunction "C_4") (pintype "passive"))
    )
    (net (code "29") (name "CH3_A") (class "Default")
      (node (ref "JP1") (pin "6") (pinfunction "6_6") (pintype "passive"))
      (node (ref "OK1") (pin "8") (pinfunction "COL_8") (pintype "passive"))
    )
    (net (code "30") (name "CH3_B") (class "Default")
      (node (ref "JP1") (pin "5") (pinfunction "5_5") (pintype "passive"))
      (node (ref "OK1") (pin "7") (pinfunction "EMIT_7") (pintype "passive"))
    )
    (net (code "31") (name "CH3_IN") (class "Default")
      (node (ref "IC5") (pin "2") (pinfunction "QC_2") (pintype "tri_state"))
      (node (ref "OK1") (pin "2") (pinfunction "C_2") (pintype "passive"))
    )
    (net (code "32") (name "CH4_A") (class "Default")
      (node (ref "JP1") (pin "8") (pinfunction "8_8") (pintype "passive"))
      (node (ref "OK1") (pin "6") (pinfunction "COL_6") (pintype "passive"))
    )
    (net (code "33") (name "CH4_B") (class "Default")
      (node (ref "JP1") (pin "7") (pinfunction "7_7") (pintype "passive"))
      (node (ref "OK1") (pin "5") (pinfunction "EMIT_5") (pintype "passive"))
    )
    (net (code "34") (name "CH4_IN") (class "Default")
      (node (ref "IC5") (pin "3") (pinfunction "QD_3") (pintype "tri_state"))
      (node (ref "OK1") (pin "4") (pinfunction "C_4") (pintype "passive"))
    )
    (net (code "35") (name "DC_VOUT") (class "Default")
      (node (ref "DCDC-3.5V") (pin "OUTP#1") (pinfunction "VOUT_OUTP#1") (pintype "bidirectional"))
      (node (ref "DCDC-3.5V") (pin "OUTP#2") (pinfunction "VOUT_OUTP#2") (pintype "bidirectional"))
      (node (ref "PWR-SWT") (pin "2") (pinfunction "2_2") (pintype "passive"))
    )
    (net (code "36") (name "DGND") (class "Default")
      (node (ref "ADE-C3") (pin "2") (pinfunction "2_2") (pintype "passive"))
      (node (ref "ADE-C4") (pin "2") (pinfunction "2_2") (pintype "passive"))
      (node (ref "ADE-C5") (pin "-") (pinfunction "-_-") (pintype "passive"))
      (node (ref "ADE-C6") (pin "2") (pinfunction "2_2") (pintype "passive"))
      (node (ref "B1") (pin "2") (pinfunction "GND_2") (pintype "bidirectional"))
      (node (ref "B1") (pin "5") (pinfunction "GND_5") (pintype "bidirectional"))
      (node (ref "B1") (pin "6") (pinfunction "GND_6") (pintype "bidirectional"))
      (node (ref "BAT1") (pin "GND") (pinfunction "-_GND") (pintype "power_in"))
      (node (ref "CC_C14") (pin "2") (pinfunction "2_2") (pintype "passive"))
      (node (ref "CC_C20") (pin "2") (pinfunction "2_2") (pintype "passive"))
      (node (ref "CC_C8") (pin "2") (pinfunction "2_2") (pintype "passive"))
      (node (ref "CC_CX1") (pin "2") (pinfunction "2_2") (pintype "passive"))
      (node (ref "CC_CX2") (pin "2") (pinfunction "2_2") (pintype "passive"))
      (node (ref "CC_DCOUP") (pin "2") (pinfunction "2_2") (pintype "passive"))
      (node (ref "DCDC-3.5V") (pin "INM#1") (pinfunction "GNDI_INM#1") (pintype "bidirectional"))
      (node (ref "DCDC-3.5V") (pin "INM#2") (pinfunction "GNDI_INM#2") (pintype "bidirectional"))
      (node (ref "DCDC-3.5V") (pin "OUTM#1") (pinfunction "GNDO_OUTM#1") (pintype "bidirectional"))
      (node (ref "DCDC-3.5V") (pin "OUTM#2") (pinfunction "GNDO_OUTM#2") (pintype "bidirectional"))
      (node (ref "ESP-C1") (pin "2") (pinfunction "2_2") (pintype "passive"))
      (node (ref "ESP-GPIO0") (pin "3") (pinfunction "3_3") (pintype "passive"))
      (node (ref "ETH-C1") (pin "1") (pinfunction "1_1") (pintype "passive"))
      (node (ref "ETH-C3") (pin "1") (pinfunction "1_1") (pintype "passive"))
      (node (ref "IC1") (pin "P$17") (pinfunction "GND_P$17") (pintype "power_in"))
      (node (ref "IC1") (pin "P$18") (pinfunction "GND_P$18") (pintype "power_in"))
      (node (ref "IC1") (pin "P$29") (pinfunction "GND_P$29") (pintype "power_in"))
      (node (ref "IC1") (pin "P$39") (pinfunction "GND_P$39") (pintype "power_in"))
      (node (ref "IC1") (pin "P$45") (pinfunction "GND_P$45") (pintype "power_in"))
      (node (ref "IC1") (pin "P$46") (pinfunction "GND_P$46") (pintype "power_in"))
      (node (ref "IC1") (pin "P$53") (pinfunction "GND_P$53") (pintype "power_in"))
      (node (ref "IC1") (pin "P$54") (pinfunction "GND_P$54") (pintype "power_in"))
      (node (ref "IC1") (pin "P$58") (pinfunction "GND_P$58") (pintype "power_in"))
      (node (ref "IC1") (pin "P$59") (pinfunction "GND_P$59") (pintype "power_in"))
      (node (ref "IC1") (pin "P$61") (pinfunction "GND_P$61") (pintype "power_in"))
      (node (ref "IC1") (pin "P$62") (pinfunction "GND_P$62") (pintype "power_in"))
      (node (ref "IC1") (pin "P$63") (pinfunction "GND_P$63") (pintype "power_in"))
      (node (ref "IC1") (pin "P$64") (pinfunction "GND_P$64") (pintype "power_in"))
      (node (ref "IC1") (pin "P$65") (pinfunction "GND_P$65") (pintype "power_in"))
      (node (ref "IC2") (pin "13") (pinfunction "G_13") (pintype "input"))
      (node (ref "IC2") (pin "8") (pinfunction "GND_8") (pintype "power_in"))
      (node (ref "IC3") (pin "13") (pinfunction "G_13") (pintype "input"))
      (node (ref "IC3") (pin "8") (pinfunction "GND_8") (pintype "power_in"))
      (node (ref "IC4") (pin "2") (pinfunction "DGND_2") (pintype "power_in"))
      (node (ref "IC4") (pin "21") (pinfunction "CS_21") (pintype "input"))
      (node (ref "IC5") (pin "13") (pinfunction "G_13") (pintype "input"))
      (node (ref "IC5") (pin "8") (pinfunction "GND_8") (pintype "power_in"))
      (node (ref "J1") (pin "P$1") (pinfunction "GND_P$1") (pintype "bidirectional"))
      (node (ref "J1") (pin "P$2") (pinfunction "GND_P$2") (pintype "bidirectional"))
      (node (ref "MQ2-R1") (pin "1") (pinfunction "1_1") (pintype "passive"))
      (node (ref "RBIAS") (pin "2") (pinfunction "2_2") (pintype "passive"))
      (node (ref "RW5500-1") (pin "1") (pinfunction "1_1") (pintype "passive"))
      (node (ref "RW5500-2") (pin "5") (pinfunction "2_5") (pintype "passive"))
      (node (ref "RW5500-2") (pin "6") (pinfunction "2_6") (pintype "passive"))
      (node (ref "RW5500-2") (pin "7") (pinfunction "2_7") (pintype "passive"))
      (node (ref "RW5500-2") (pin "8") (pinfunction "2_8") (pintype "passive"))
      (node (ref "S1") (pin "3") (pinfunction "3_3") (pintype "passive"))
      (node (ref "S1") (pin "4") (pinfunction "4_4") (pintype "passive"))
      (node (ref "SENSOR-DHT") (pin "4") (pinfunction "4_4") (pintype "passive"))
      (node (ref "SENSOR-MQ2") (pin "HB") (pinfunction "HB_HB") (pintype "bidirectional"))
      (node (ref "SIM900-C1") (pin "-") (pinfunction "-_-") (pintype "passive"))
      (node (ref "SIM900-C2") (pin "-") (pinfunction "-_-") (pintype "passive"))
      (node (ref "SIM900-C3") (pin "2") (pinfunction "2_2") (pintype "passive"))
      (node (ref "SIM900-C4") (pin "2") (pinfunction "2_2") (pintype "passive"))
      (node (ref "SIM900-C5") (pin "2") (pinfunction "2_2") (pintype "passive"))
      (node (ref "SIM900-R6") (pin "2") (pinfunction "2_2") (pintype "passive"))
      (node (ref "SIM900-R9") (pin "2") (pinfunction "2_2") (pintype "passive"))
      (node (ref "SIM900-T1") (pin "E") (pinfunction "E_E") (pintype "passive"))
      (node (ref "SIM900-T2") (pin "E") (pinfunction "E_E") (pintype "passive"))
      (node (ref "SIM900-T3") (pin "E") (pinfunction "E_E") (pintype "passive"))
      (node (ref "SIM900-T4") (pin "E") (pinfunction "E_E") (pintype "passive"))
      (node (ref "SIM_C1") (pin "1") (pinfunction "1_1") (pintype "passive"))
      (node (ref "SIM_C2") (pin "1") (pinfunction "1_1") (pintype "passive"))
      (node (ref "SR_OUT1") (pin "2") (pinfunction "2_2") (pintype "passive"))
      (node (ref "SR_OUT2") (pin "2") (pinfunction "2_2") (pintype "passive"))
      (node (ref "STM-C1") (pin "1") (pinfunction "1_1") (pintype "passive"))
      (node (ref "STM-C10") (pin "2") (pinfunction "2_2") (pintype "passive"))
      (node (ref "STM-C11") (pin "2") (pinfunction "2_2") (pintype "passive"))
      (node (ref "STM-C12") (pin "2") (pinfunction "2_2") (pintype "passive"))
      (node (ref "STM-C13") (pin "2") (pinfunction "2_2") (pintype "passive"))
      (node (ref "STM-C2") (pin "1") (pinfunction "1_1") (pintype "passive"))
      (node (ref "STM-C3") (pin "1") (pinfunction "1_1") (pintype "passive"))
      (node (ref "STM-C8") (pin "2") (pinfunction "2_2") (pintype "passive"))
      (node (ref "STM-SWD") (pin "3") (pinfunction "3_3") (pintype "passive"))
      (node (ref "STM-USART") (pin "4") (pinfunction "4_4") (pintype "passive"))
      (node (ref "STM_CHIP") (pin "18") (pinfunction "VSS_4_18") (pintype "power_in"))
      (node (ref "STM_CHIP") (pin "31") (pinfunction "VSS_1_31") (pintype "power_in"))
      (node (ref "STM_CHIP") (pin "47") (pinfunction "VSS_2_47") (pintype "power_in"))
      (node (ref "STM_CHIP") (pin "63") (pinfunction "VSS_3_63") (pintype "power_in"))
      (node (ref "SYS-C1") (pin "2") (pinfunction "2_2") (pintype "passive"))
      (node (ref "SYS-C3") (pin "2") (pinfunction "2_2") (pintype "passive"))
      (node (ref "SYS-L1") (pin "2") (pinfunction "2_2") (pintype "passive"))
      (node (ref "U$13") (pin "LCD_GND") (pinfunction "LCD_GND_LCD_GND") (pintype "power_in"))
      (node (ref "U$13") (pin "T_CS") (pinfunction "T_CS_T_CS") (pintype "bidirectional"))
      (node (ref "U$4") (pin "3") (pinfunction "CS_3") (pintype "input"))
      (node (ref "U$5") (pin "GND") (pinfunction "GND_GND") (pintype "bidirectional"))
      (node (ref "U$5") (pin "GPIO15") (pinfunction "GPIO15_GPIO15") (pintype "bidirectional"))
      (node (ref "U$7") (pin "P$1") (pinfunction "GND_P$1") (pintype "bidirectional"))
      (node (ref "U$7") (pin "P$2") (pinfunction "GND_P$2") (pintype "bidirectional"))
      (node (ref "U$8") (pin "SHIELD_GND$1") (pinfunction "GND$1_SHIELD_GND$1") (pintype "bidirectional"))
      (node (ref "U$8") (pin "SHIELD_GND$2") (pinfunction "GND$2_SHIELD_GND$2") (pintype "bidirectional"))
      (node (ref "U$8") (pin "SIM_GND") (pinfunction "SIM_GND_SIM_GND") (pintype "bidirectional"))
      (node (ref "U2") (pin "14") (pinfunction "AGND_14") (pintype "passive"))
      (node (ref "U2") (pin "16") (pinfunction "AGND_16") (pintype "passive"))
      (node (ref "U2") (pin "19") (pinfunction "AGND_19") (pintype "passive"))
      (node (ref "U2") (pin "29") (pinfunction "GND_29") (pintype "passive"))
      (node (ref "U2") (pin "3") (pinfunction "AGND_3") (pintype "passive"))
      (node (ref "U2") (pin "48") (pinfunction "AGND_48") (pintype "passive"))
      (node (ref "U2") (pin "9") (pinfunction "AGND_9") (pintype "passive"))
      (node (ref "USB_IN") (pin "GND1") (pinfunction "GND_GND1") (pintype "bidirectional"))
      (node (ref "USB_IN") (pin "SHIELD1") (pinfunction "SHIELD_SHIELD1") (pintype "bidirectional"))
      (node (ref "USB_IN") (pin "SHIELD2") (pinfunction "SHIELD_SHIELD2") (pintype "bidirectional"))
      (node (ref "USB_IN") (pin "SHIELD3") (pinfunction "SHIELD_SHIELD3") (pintype "bidirectional"))
      (node (ref "W5500-C1") (pin "2") (pinfunction "2_2") (pintype "passive"))
      (node (ref "W5500-C10") (pin "2") (pinfunction "2_2") (pintype "passive"))
      (node (ref "W5500-C11") (pin "2") (pinfunction "2_2") (pintype "passive"))
      (node (ref "W5500-C12") (pin "-") (pinfunction "-_-") (pintype "passive"))
      (node (ref "W5500-C13") (pin "-") (pinfunction "-_-") (pintype "passive"))
      (node (ref "W5500-C2") (pin "2") (pinfunction "2_2") (pintype "passive"))
      (node (ref "W5500-C3") (pin "2") (pinfunction "2_2") (pintype "passive"))
      (node (ref "W5500-C4") (pin "2") (pinfunction "2_2") (pintype "passive"))
      (node (ref "W5500-C5") (pin "2") (pinfunction "2_2") (pintype "passive"))
      (node (ref "W5500-C6") (pin "2") (pinfunction "2_2") (pintype "passive"))
      (node (ref "W5500-C7") (pin "2") (pinfunction "2_2") (pintype "passive"))
      (node (ref "W5500-C8") (pin "2") (pinfunction "2_2") (pintype "passive"))
      (node (ref "W5500-C9") (pin "2") (pinfunction "2_2") (pintype "passive"))
      (node (ref "W5500-R11") (pin "1") (pinfunction "1_1") (pintype "passive"))
      (node (ref "W5500-R12") (pin "1") (pinfunction "1_1") (pintype "passive"))
    )
    (net (code "37") (name "DHT_DATA") (class "Default")
      (node (ref "DHT-R1") (pin "2") (pinfunction "2_2") (pintype "passive"))
      (node (ref "SENSOR-DHT") (pin "2") (pinfunction "2_2") (pintype "passive"))
      (node (ref "STM_CHIP") (pin "54") (pinfunction "PD2_54") (pintype "bidirectional"))
    )
    (net (code "38") (name "ESP_GPIO0") (class "Default")
      (node (ref "ESP-GPIO0") (pin "2") (pinfunction "2_2") (pintype "passive"))
      (node (ref "U$5") (pin "GPIO00") (pinfunction "GPIO0_GPIO00") (pintype "bidirectional"))
    )
    (net (code "39") (name "ESP_RX") (class "Default")
      (node (ref "ESP_EXT") (pin "3") (pinfunction "3_3") (pintype "passive"))
      (node (ref "JP_ESP_RX") (pin "1") (pinfunction "1_1") (pintype "passive"))
      (node (ref "U$5") (pin "RXD") (pinfunction "RXD_RXD") (pintype "bidirectional"))
    )
    (net (code "40") (name "ESP_TX") (class "Default")
      (node (ref "ESP_EXT") (pin "4") (pinfunction "4_4") (pintype "passive"))
      (node (ref "JP_ESP_TX") (pin "1") (pinfunction "1_1") (pintype "passive"))
      (node (ref "U$5") (pin "TXD") (pinfunction "TXD_TXD") (pintype "bidirectional"))
    )
    (net (code "41") (name "ETH_CS") (class "Default")
      (node (ref "STM_CHIP") (pin "33") (pinfunction "PB12_33") (pintype "bidirectional"))
      (node (ref "U2") (pin "32") (pinfunction "SCS_N_32") (pintype "passive"))
      (node (ref "W5500-R13") (pin "1") (pinfunction "1_1") (pintype "passive"))
    )
    (net (code "42") (name "ETH_MISO") (class "Default")
      (node (ref "STM_CHIP") (pin "35") (pinfunction "PB14_35") (pintype "bidirectional"))
      (node (ref "U2") (pin "34") (pinfunction "MISO_34") (pintype "passive"))
    )
    (net (code "43") (name "ETH_MOSI") (class "Default")
      (node (ref "STM_CHIP") (pin "36") (pinfunction "PB15_36") (pintype "bidirectional"))
      (node (ref "U2") (pin "35") (pinfunction "MOSI_35") (pintype "passive"))
    )
    (net (code "44") (name "ETH_RSTN") (class "Default")
      (node (ref "RW5500-3") (pin "2") (pinfunction "2_2") (pintype "passive"))
      (node (ref "STM_CHIP") (pin "37") (pinfunction "PC6_37") (pintype "bidirectional"))
      (node (ref "U2") (pin "37") (pinfunction "RST_N_37") (pintype "passive"))
    )
    (net (code "45") (name "ETH_SCK") (class "Default")
      (node (ref "STM_CHIP") (pin "34") (pinfunction "PB13_34") (pintype "bidirectional"))
      (node (ref "U2") (pin "33") (pinfunction "SCLK_33") (pintype "passive"))
    )
    (net (code "46") (name "LCD_CS") (class "Default")
      (node (ref "STM_CHIP") (pin "20") (pinfunction "PA4_20") (pintype "bidirectional"))
      (node (ref "U$13") (pin "LCD_CS") (pinfunction "LCD_CS_LCD_CS") (pintype "bidirectional"))
    )
    (net (code "47") (name "LCD_D{slash}C") (class "Default")
      (node (ref "STM_CHIP") (pin "24") (pinfunction "PC4_24") (pintype "bidirectional"))
      (node (ref "U$13") (pin "LCD_D/C") (pinfunction "LCD_D/C_LCD_D/C") (pintype "bidirectional"))
    )
    (net (code "48") (name "LCD_LED") (class "Default")
      (node (ref "LCD-R1") (pin "1") (pinfunction "1_1") (pintype "passive"))
      (node (ref "U$13") (pin "LED") (pinfunction "LCD_LED_LED") (pintype "bidirectional"))
    )
    (net (code "49") (name "LCD_MISO") (class "Default")
      (node (ref "STM_CHIP") (pin "22") (pinfunction "PA6_22") (pintype "bidirectional"))
      (node (ref "U$13") (pin "LCD_MISO") (pinfunction "LCD_MISO_LCD_MISO") (pintype "bidirectional"))
      (node (ref "U$13") (pin "SD_MISO") (pinfunction "SD_MISO_SD_MISO") (pintype "bidirectional"))
    )
    (net (code "50") (name "LCD_MOSI") (class "Default")
      (node (ref "STM_CHIP") (pin "23") (pinfunction "PA7_23") (pintype "bidirectional"))
      (node (ref "U$13") (pin "LCD_MOSI") (pinfunction "LCD_MOSI_LCD_MOSI") (pintype "bidirectional"))
      (node (ref "U$13") (pin "SD_MOSI") (pinfunction "SD_MOSI_SD_MOSI") (pintype "bidirectional"))
    )
    (net (code "51") (name "LCD_RESET") (class "Default")
      (node (ref "STM_CHIP") (pin "25") (pinfunction "PC5_25") (pintype "bidirectional"))
      (node (ref "U$13") (pin "LCD_RESET") (pinfunction "LCD_RESET_LCD_RESET") (pintype "bidirectional"))
    )
    (net (code "52") (name "LCD_SCK") (class "Default")
      (node (ref "STM_CHIP") (pin "21") (pinfunction "PA5_21") (pintype "bidirectional"))
      (node (ref "U$13") (pin "LCD_SCK") (pinfunction "LCD_SCK_LCD_SCK") (pintype "bidirectional"))
      (node (ref "U$13") (pin "SD_SCK") (pinfunction "SD_SCK_SD_SCK") (pintype "bidirectional"))
    )
    (net (code "53") (name "LINKLED") (class "Default")
      (node (ref "ETH-R5") (pin "1") (pinfunction "1_1") (pintype "passive"))
      (node (ref "U2") (pin "25") (pinfunction "LINKLED_25") (pintype "passive"))
    )
    (net (code "54") (name "MQ2_DATA") (class "Default")
      (node (ref "MQ2-R1") (pin "2") (pinfunction "2_2") (pintype "passive"))
      (node (ref "SENSOR-MQ2") (pin "B1") (pinfunction "B1_B1") (pintype "bidirectional"))
      (node (ref "SENSOR-MQ2") (pin "B2") (pinfunction "B2_B2") (pintype "bidirectional"))
      (node (ref "STM_CHIP") (pin "26") (pinfunction "PB0_26") (pintype "bidirectional"))
    )
    (net (code "55") (name "Net-(ADE-R1-Pad1)") (class "Default")
      (node (ref "ADE-R1") (pin "1") (pinfunction "1_1") (pintype "passive"))
      (node (ref "RTO1") (pin "2") (pinfunction "2_2") (pintype "passive"))
      (node (ref "U$9") (pin "OA") (pinfunction "OA_OA") (pintype "bidirectional"))
    )
    (net (code "56") (name "Net-(ADE-R2-Pad1)") (class "Default")
      (node (ref "ADE-R2") (pin "1") (pinfunction "1_1") (pintype "passive"))
      (node (ref "RTO2") (pin "2") (pinfunction "2_2") (pintype "passive"))
      (node (ref "U$10") (pin "OA") (pinfunction "OA_OA") (pintype "bidirectional"))
    )
    (net (code "57") (name "Net-(ADE-R3-Pad1)") (class "Default")
      (node (ref "ADE-R3") (pin "1") (pinfunction "1_1") (pintype "passive"))
      (node (ref "RTO3") (pin "2") (pinfunction "2_2") (pintype "passive"))
      (node (ref "U$11") (pin "OA") (pinfunction "OA_OA") (pintype "bidirectional"))
    )
    (net (code "58") (name "Net-(ADE-R7-Pad1)") (class "Default")
      (node (ref "ADE-R7") (pin "1") (pinfunction "1_1") (pintype "passive"))
      (node (ref "RTO1") (pin "1") (pinfunction "1_1") (pintype "passive"))
      (node (ref "RTO2") (pin "1") (pinfunction "1_1") (pintype "passive"))
      (node (ref "RTO3") (pin "1") (pinfunction "1_1") (pintype "passive"))
      (node (ref "U$10") (pin "OB") (pinfunction "OB_OB") (pintype "bidirectional"))
      (node (ref "U$11") (pin "OB") (pinfunction "OB_OB") (pintype "bidirectional"))
      (node (ref "U$9") (pin "OB") (pinfunction "OB_OB") (pintype "bidirectional"))
    )
    (net (code "59") (name "Net-(ADE-R8-Pad2)") (class "Default")
      (node (ref "ADE-R8") (pin "2") (pinfunction "2_2") (pintype "passive"))
      (node (ref "ADE-R9") (pin "1") (pinfunction "1_1") (pintype "passive"))
      (node (ref "JP2") (pin "SLEEVE") (pinfunction "SLEEVE_SLEEVE") (pintype "bidirectional"))
    )
    (net (code "60") (name "Net-(ADE-R11-Pad2)") (class "Default")
      (node (ref "ADE-R11") (pin "2") (pinfunction "2_2") (pintype "passive"))
      (node (ref "ADE-R12") (pin "1") (pinfunction "1_1") (pintype "passive"))
      (node (ref "JP3") (pin "SLEEVE") (pinfunction "SLEEVE_SLEEVE") (pintype "bidirectional"))
    )
    (net (code "61") (name "Net-(ADE-R14-Pad2)") (class "Default")
      (node (ref "ADE-R14") (pin "2") (pinfunction "2_2") (pintype "passive"))
      (node (ref "ADE-R15") (pin "1") (pinfunction "1_1") (pintype "passive"))
      (node (ref "JP4") (pin "SLEEVE") (pinfunction "SLEEVE_SLEEVE") (pintype "bidirectional"))
    )
    (net (code "62") (name "Net-(B1-ANT)") (class "Default")
      (node (ref "B1") (pin "1") (pinfunction "ANT_1") (pintype "bidirectional"))
      (node (ref "J1") (pin "P$3") (pinfunction "SIGNAL_P$3") (pintype "bidirectional"))
    )
    (net (code "63") (name "Net-(B1-BAL_N)") (class "Default")
      (node (ref "B1") (pin "3") (pinfunction "BAL_N_3") (pintype "bidirectional"))
      (node (ref "U$4") (pin "19") (pinfunction "RF-N_19") (pintype "bidirectional"))
    )
    (net (code "64") (name "Net-(B1-BAL_P)") (class "Default")
      (node (ref "B1") (pin "4") (pinfunction "BAL_P_4") (pintype "bidirectional"))
      (node (ref "U$4") (pin "17") (pinfunction "RF-P_17") (pintype "bidirectional"))
    )
    (net (code "65") (name "Net-(ETHERNET-LED1_K)") (class "Default")
      (node (ref "ETH-R4") (pin "2") (pinfunction "2_2") (pintype "passive"))
      (node (ref "ETHERNET") (pin "10") (pinfunction "LED1_K_10") (pintype "bidirectional"))
    )
    (net (code "66") (name "Net-(ETHERNET-LED2_K)") (class "Default")
      (node (ref "ETH-R5") (pin "2") (pinfunction "2_2") (pintype "passive"))
      (node (ref "ETHERNET") (pin "11") (pinfunction "LED2_K_11") (pintype "bidirectional"))
    )
    (net (code "67") (name "Net-(ETHERNET-RCT)") (class "Default")
      (node (ref "ETH-C3") (pin "2") (pinfunction "2_2") (pintype "passive"))
      (node (ref "ETH-R6") (pin "1") (pinfunction "1_1") (pintype "passive"))
      (node (ref "ETH-R7") (pin "2") (pinfunction "2_2") (pintype "passive"))
      (node (ref "ETHERNET") (pin "6") (pinfunction "RCT_6") (pintype "bidirectional"))
    )
    (net (code "68") (name "Net-(ETHERNET-RX+)") (class "Default")
      (node (ref "ETH-C2") (pin "1") (pinfunction "1_1") (pintype "passive"))
      (node (ref "ETHERNET") (pin "7") (pinfunction "RX+_7") (pintype "bidirectional"))
    )
    (net (code "69") (name "Net-(ETHERNET-RX-)") (class "Default")
      (node (ref "ETH-C4") (pin "1") (pinfunction "1_1") (pintype "passive"))
      (node (ref "ETHERNET") (pin "8") (pinfunction "RX-_8") (pintype "bidirectional"))
    )
    (net (code "70") (name "Net-(ETHERNET-TCT)") (class "Default")
      (node (ref "ETH-C1") (pin "2") (pinfunction "2_2") (pintype "passive"))
      (node (ref "ETH-R3") (pin "1") (pinfunction "1_1") (pintype "passive"))
      (node (ref "ETHERNET") (pin "3") (pinfunction "TCT_3") (pintype "bidirectional"))
    )
    (net (code "71") (name "Net-(IC1-RF_ANT)") (class "Default")
      (node (ref "IC1") (pin "P$60") (pinfunction "RF_ANT_P$60") (pintype "bidirectional"))
      (node (ref "U$7") (pin "P$3") (pinfunction "SIGNAL_P$3") (pintype "bidirectional"))
    )
    (net (code "72") (name "Net-(IC1-SIM_CLK)") (class "Default")
      (node (ref "IC1") (pin "P$32") (pinfunction "SIM_CLK_P$32") (pintype "bidirectional"))
      (node (ref "SIM900-R2") (pin "1") (pinfunction "1_1") (pintype "passive"))
    )
    (net (code "73") (name "Net-(IC1-SIM_DATA)") (class "Default")
      (node (ref "IC1") (pin "P$31") (pinfunction "SIM_DATA_P$31") (pintype "bidirectional"))
      (node (ref "SIM900-R3") (pin "1") (pinfunction "1_1") (pintype "passive"))
    )
    (net (code "74") (name "Net-(IC1-SIM_RST)") (class "Default")
      (node (ref "IC1") (pin "P$33") (pinfunction "SIM_RST_P$33") (pintype "bidirectional"))
      (node (ref "SIM900-R1") (pin "1") (pinfunction "1_1") (pintype "passive"))
    )
    (net (code "75") (name "Net-(IC1-VBAT1)") (class "Default")
      (node (ref "IC1") (pin "P$55") (pinfunction "VBAT1_P$55") (pintype "power_in"))
      (node (ref "IC1") (pin "P$56") (pinfunction "VBAT2_P$56") (pintype "power_in"))
      (node (ref "IC1") (pin "P$57") (pinfunction "VBAT3_P$57") (pintype "power_in"))
      (node (ref "SIM900-C1") (pin "+") (pinfunction "+_+") (pintype "passive"))
      (node (ref "SIM900-C2") (pin "+") (pinfunction "+_+") (pintype "passive"))
      (node (ref "SYS-L2") (pin "1") (pinfunction "1_1") (pintype "passive"))
    )
    (net (code "76") (name "Net-(IC1-VRTC)") (class "Default")
      (node (ref "IC1") (pin "P$26") (pinfunction "VRTC_P$26") (pintype "power_in"))
      (node (ref "SIM900-C3") (pin "1") (pinfunction "1_1") (pintype "passive"))
    )
    (net (code "77") (name "Net-(IC4A-CLKIN)") (class "Default")
      (node (ref "ADE-C3") (pin "1") (pinfunction "1_1") (pintype "passive"))
      (node (ref "ADE-XTAL") (pin "1") (pinfunction "1_1") (pintype "passive"))
      (node (ref "IC4") (pin "19") (pinfunction "CLKIN_19") (pintype "input"))
    )
    (net (code "78") (name "Net-(IC4A-CLKOUT)") (class "Default")
      (node (ref "ADE-C4") (pin "1") (pinfunction "1_1") (pintype "passive"))
      (node (ref "ADE-XTAL") (pin "2") (pinfunction "2_2") (pintype "passive"))
      (node (ref "IC4") (pin "20") (pinfunction "CLKOUT_20") (pintype "output"))
    )
    (net (code "79") (name "Net-(IC4C-IN)") (class "Default")
      (node (ref "ADE-C12") (pin "1") (pinfunction "1_1") (pintype "passive"))
      (node (ref "ADE-R10") (pin "2") (pinfunction "2_2") (pintype "passive"))
      (node (ref "IC4") (pin "6") (pinfunction "IN_6") (pintype "input"))
    )
    (net (code "80") (name "Net-(IC4C-IP)") (class "Default")
      (node (ref "ADE-C11") (pin "1") (pinfunction "1_1") (pintype "passive"))
      (node (ref "ADE-R9") (pin "2") (pinfunction "2_2") (pintype "passive"))
      (node (ref "IC4") (pin "5") (pinfunction "IP_5") (pintype "input"))
    )
    (net (code "81") (name "Net-(IC4D-IN)") (class "Default")
      (node (ref "ADE-C14") (pin "1") (pinfunction "1_1") (pintype "passive"))
      (node (ref "ADE-R13") (pin "2") (pinfunction "2_2") (pintype "passive"))
      (node (ref "IC4") (pin "8") (pinfunction "IN_8") (pintype "input"))
    )
    (net (code "82") (name "Net-(IC4D-IP)") (class "Default")
      (node (ref "ADE-C13") (pin "1") (pinfunction "1_1") (pintype "passive"))
      (node (ref "ADE-R12") (pin "2") (pinfunction "2_2") (pintype "passive"))
      (node (ref "IC4") (pin "7") (pinfunction "IP_7") (pintype "input"))
    )
    (net (code "83") (name "Net-(IC4E-IN)") (class "Default")
      (node (ref "ADE-C16") (pin "1") (pinfunction "1_1") (pintype "passive"))
      (node (ref "ADE-R16") (pin "2") (pinfunction "2_2") (pintype "passive"))
      (node (ref "IC4") (pin "10") (pinfunction "IN_10") (pintype "input"))
    )
    (net (code "84") (name "Net-(IC4E-IP)") (class "Default")
      (node (ref "ADE-C15") (pin "1") (pinfunction "1_1") (pintype "passive"))
      (node (ref "ADE-R15") (pin "2") (pinfunction "2_2") (pintype "passive"))
      (node (ref "IC4") (pin "9") (pinfunction "IP_9") (pintype "input"))
    )
    (net (code "85") (name "Net-(IC4F-REF)") (class "Default")
      (node (ref "ADE-C1") (pin "1") (pinfunction "1_1") (pintype "passive"))
      (node (ref "ADE-C2") (pin "1") (pinfunction "1_1") (pintype "passive"))
      (node (ref "IC4") (pin "12") (pinfunction "REF_12") (pintype "bidirectional"))
    )
    (net (code "86") (name "Net-(IC4G-VAP)") (class "Default")
      (node (ref "ADE-C7") (pin "1") (pinfunction "1_1") (pintype "passive"))
      (node (ref "ADE-R1") (pin "2") (pinfunction "2_2") (pintype "passive"))
      (node (ref "ADE-R4") (pin "2") (pinfunction "2_2") (pintype "passive"))
      (node (ref "IC4") (pin "16") (pinfunction "VAP_16") (pintype "input"))
    )
    (net (code "87") (name "Net-(IC4G-VBP)") (class "Default")
      (node (ref "ADE-C8") (pin "1") (pinfunction "1_1") (pintype "passive"))
      (node (ref "ADE-R2") (pin "2") (pinfunction "2_2") (pintype "passive"))
      (node (ref "ADE-R5") (pin "2") (pinfunction "2_2") (pintype "passive"))
      (node (ref "IC4") (pin "15") (pinfunction "VBP_15") (pintype "input"))
    )
    (net (code "88") (name "Net-(IC4G-VCP)") (class "Default")
      (node (ref "ADE-C9") (pin "1") (pinfunction "1_1") (pintype "passive"))
      (node (ref "ADE-R3") (pin "2") (pinfunction "2_2") (pintype "passive"))
      (node (ref "ADE-R6") (pin "2") (pinfunction "2_2") (pintype "passive"))
      (node (ref "IC4") (pin "14") (pinfunction "VCP_14") (pintype "input"))
    )
    (net (code "89") (name "Net-(IC4G-VN)") (class "Default")
      (node (ref "ADE-C10") (pin "1") (pinfunction "1_1") (pintype "passive"))
      (node (ref "ADE-R7") (pin "2") (pinfunction "2_2") (pintype "passive"))
      (node (ref "IC4") (pin "13") (pinfunction "VN_13") (pintype "input"))
    )
    (net (code "90") (name "Net-(JP2-LEFT)") (class "Default")
      (node (ref "ADE-R10") (pin "1") (pinfunction "1_1") (pintype "passive"))
      (node (ref "ADE-R8") (pin "1") (pinfunction "1_1") (pintype "passive"))
      (node (ref "JP2") (pin "RING") (pinfunction "RIGHT_RING") (pintype "bidirectional"))
      (node (ref "JP2") (pin "TIP") (pinfunction "LEFT_TIP") (pintype "bidirectional"))
    )
    (net (code "91") (name "Net-(JP3-LEFT)") (class "Default")
      (node (ref "ADE-R11") (pin "1") (pinfunction "1_1") (pintype "passive"))
      (node (ref "ADE-R13") (pin "1") (pinfunction "1_1") (pintype "passive"))
      (node (ref "JP3") (pin "RING") (pinfunction "RIGHT_RING") (pintype "bidirectional"))
      (node (ref "JP3") (pin "TIP") (pinfunction "LEFT_TIP") (pintype "bidirectional"))
    )
    (net (code "92") (name "Net-(JP4-LEFT)") (class "Default")
      (node (ref "ADE-R14") (pin "1") (pinfunction "1_1") (pintype "passive"))
      (node (ref "ADE-R16") (pin "1") (pinfunction "1_1") (pintype "passive"))
      (node (ref "JP4") (pin "RING") (pinfunction "RIGHT_RING") (pintype "bidirectional"))
      (node (ref "JP4") (pin "TIP") (pinfunction "LEFT_TIP") (pintype "bidirectional"))
    )
    (net (code "93") (name "Net-(OK1A-A)") (class "Default")
      (node (ref "OK1") (pin "1") (pinfunction "A_1") (pintype "passive"))
      (node (ref "R_CH3") (pin "2") (pinfunction "2_2") (pintype "passive"))
    )
    (net (code "94") (name "Net-(OK1B-A)") (class "Default")
      (node (ref "OK1") (pin "3") (pinfunction "A_3") (pintype "passive"))
      (node (ref "R_CH4") (pin "2") (pinfunction "2_2") (pintype "passive"))
    )
    (net (code "95") (name "Net-(OK2A-A)") (class "Default")
      (node (ref "OK2") (pin "1") (pinfunction "A_1") (pintype "passive"))
      (node (ref "R_CH1") (pin "2") (pinfunction "2_2") (pintype "passive"))
    )
    (net (code "96") (name "Net-(OK2B-A)") (class "Default")
      (node (ref "OK2") (pin "3") (pinfunction "A_3") (pintype "passive"))
      (node (ref "R_CH2") (pin "2") (pinfunction "2_2") (pintype "passive"))
    )
    (net (code "97") (name "Net-(RT1-Pad2)") (class "Default")
      (node (ref "RT1") (pin "2") (pinfunction "2_2") (pintype "passive"))
      (node (ref "U$9") (pin "IA") (pinfunction "IA_IA") (pintype "bidirectional"))
    )
    (net (code "98") (name "Net-(RT2-Pad2)") (class "Default")
      (node (ref "RT2") (pin "2") (pinfunction "2_2") (pintype "passive"))
      (node (ref "U$10") (pin "IA") (pinfunction "IA_IA") (pintype "bidirectional"))
    )
    (net (code "99") (name "Net-(RT3-Pad2)") (class "Default")
      (node (ref "RT3") (pin "2") (pinfunction "2_2") (pintype "passive"))
      (node (ref "U$11") (pin "IA") (pinfunction "IA_IA") (pintype "bidirectional"))
    )
    (net (code "100") (name "Net-(RW5500-1A-2)") (class "Default")
      (node (ref "RW5500-1") (pin "8") (pinfunction "2_8") (pintype "passive"))
      (node (ref "U2") (pin "42") (pinfunction "RSVD_42") (pintype "passive"))
    )
    (net (code "101") (name "Net-(RW5500-1B-2)") (class "Default")
      (node (ref "RW5500-1") (pin "7") (pinfunction "2_7") (pintype "passive"))
      (node (ref "U2") (pin "43") (pinfunction "PMODE2_43") (pintype "passive"))
    )
    (net (code "102") (name "Net-(RW5500-1C-2)") (class "Default")
      (node (ref "RW5500-1") (pin "6") (pinfunction "2_6") (pintype "passive"))
      (node (ref "U2") (pin "44") (pinfunction "PMODE1_44") (pintype "passive"))
    )
    (net (code "103") (name "Net-(RW5500-1D-2)") (class "Default")
      (node (ref "RW5500-1") (pin "5") (pinfunction "2_5") (pintype "passive"))
      (node (ref "U2") (pin "45") (pinfunction "PMODE0_45") (pintype "passive"))
    )
    (net (code "104") (name "Net-(RW5500-2-Pad1)") (class "Default")
      (node (ref "RW5500-2") (pin "1") (pinfunction "1_1") (pintype "passive"))
      (node (ref "U2") (pin "41") (pinfunction "RSVD_41") (pintype "passive"))
    )
    (net (code "105") (name "Net-(RW5500-2B-1)") (class "Default")
      (node (ref "RW5500-2") (pin "2") (pinfunction "1_2") (pintype "passive"))
      (node (ref "U2") (pin "40") (pinfunction "RSVD_40") (pintype "passive"))
    )
    (net (code "106") (name "Net-(RW5500-2C-1)") (class "Default")
      (node (ref "RW5500-2") (pin "3") (pinfunction "1_3") (pintype "passive"))
      (node (ref "U2") (pin "39") (pinfunction "RSVD_39") (pintype "passive"))
    )
    (net (code "107") (name "Net-(RW5500-2D-1)") (class "Default")
      (node (ref "RW5500-2") (pin "4") (pinfunction "1_4") (pintype "passive"))
      (node (ref "U2") (pin "38") (pinfunction "RSVD_38") (pintype "passive"))
    )
    (net (code "108") (name "Net-(SIM900-LED1-PadA)") (class "Default")
      (node (ref "SIM900-LED1") (pin "A") (pinfunction "A_A") (pintype "passive"))
      (node (ref "SIM900-R4") (pin "1") (pinfunction "1_1") (pintype "passive"))
    )
    (net (code "109") (name "Net-(SIM900-LED1-PadC)") (class "Default")
      (node (ref "SIM900-LED1") (pin "C") (pinfunction "C_C") (pintype "passive"))
      (node (ref "SIM900-T1") (pin "C") (pinfunction "C_C") (pintype "passive"))
    )
    (net (code "110") (name "Net-(SIM900-LED2-PadA)") (class "Default")
      (node (ref "SIM900-LED2") (pin "A") (pinfunction "A_A") (pintype "passive"))
      (node (ref "SIM900-R7") (pin "1") (pinfunction "1_1") (pintype "passive"))
    )
    (net (code "111") (name "Net-(SIM900-LED2-PadC)") (class "Default")
      (node (ref "SIM900-LED2") (pin "C") (pinfunction "C_C") (pintype "passive"))
      (node (ref "SIM900-T2") (pin "C") (pinfunction "C_C") (pintype "passive"))
    )
    (net (code "112") (name "Net-(SIM900-R5-Pad1)") (class "Default")
      (node (ref "SIM900-R5") (pin "1") (pinfunction "1_1") (pintype "passive"))
      (node (ref "SIM900-R6") (pin "1") (pinfunction "1_1") (pintype "passive"))
      (node (ref "SIM900-T1") (pin "B") (pinfunction "B_B") (pintype "passive"))
    )
    (net (code "113") (name "Net-(SIM900-R8-Pad1)") (class "Default")
      (node (ref "SIM900-R8") (pin "1") (pinfunction "1_1") (pintype "passive"))
      (node (ref "SIM900-R9") (pin "1") (pinfunction "1_1") (pintype "passive"))
      (node (ref "SIM900-T2") (pin "B") (pinfunction "B_B") (pintype "passive"))
    )
    (net (code "114") (name "Net-(SIM900-R10-Pad2)") (class "Default")
      (node (ref "SIM900-R10") (pin "2") (pinfunction "2_2") (pintype "passive"))
      (node (ref "SIM900-T3") (pin "B") (pinfunction "B_B") (pintype "passive"))
    )
    (net (code "115") (name "Net-(SIM900-R11-Pad2)") (class "Default")
      (node (ref "SIM900-R11") (pin "2") (pinfunction "2_2") (pintype "passive"))
      (node (ref "SIM900-T4") (pin "B") (pinfunction "B_B") (pintype "passive"))
    )
    (net (code "116") (name "Net-(STM_CHIP-PA2)") (class "Default")
      (node (ref "JP_ESP_RX") (pin "2") (pinfunction "2_2") (pintype "passive"))
      (node (ref "STM_CHIP") (pin "16") (pinfunction "PA2_16") (pintype "bidirectional"))
    )
    (net (code "117") (name "Net-(STM_CHIP-PA3)") (class "Default")
      (node (ref "JP_ESP_TX") (pin "2") (pinfunction "2_2") (pintype "passive"))
      (node (ref "STM_CHIP") (pin "17") (pinfunction "PA3_17") (pintype "bidirectional"))
    )
    (net (code "118") (name "Net-(STM_CHIP-PC14-OSC32_IN)") (class "Default")
      (node (ref "STM-C2") (pin "2") (pinfunction "2_2") (pintype "passive"))
      (node (ref "STM-XTAL") (pin "2") (pinfunction "2_2") (pintype "passive"))
      (node (ref "STM_CHIP") (pin "3") (pinfunction "PC14-OSC32_IN_3") (pintype "bidirectional"))
    )
    (net (code "119") (name "Net-(STM_CHIP-PC15-OSC32_OUT)") (class "Default")
      (node (ref "STM-C3") (pin "2") (pinfunction "2_2") (pintype "passive"))
      (node (ref "STM-XTAL") (pin "1") (pinfunction "1_1") (pintype "passive"))
      (node (ref "STM_CHIP") (pin "4") (pinfunction "PC15-OSC32_OUT_4") (pintype "bidirectional"))
    )
    (net (code "120") (name "Net-(U$4B-DCOUPL)") (class "Default")
      (node (ref "CC_DCOUP") (pin "1") (pinfunction "1_1") (pintype "passive"))
      (node (ref "U$4") (pin "27") (pinfunction "DCOUPL_27") (pintype "power_in"))
    )
    (net (code "121") (name "Net-(U$4C-RBIAS)") (class "Default")
      (node (ref "RBIAS") (pin "1") (pinfunction "1_1") (pintype "passive"))
      (node (ref "U$4") (pin "23") (pinfunction "RBIAS_23") (pintype "bidirectional"))
    )
    (net (code "122") (name "Net-(U$4C-VREG-EN)") (class "Default")
      (node (ref "R_VREG") (pin "1") (pinfunction "1_1") (pintype "passive"))
      (node (ref "U$4") (pin "26") (pinfunction "VREG-EN_26") (pintype "input"))
    )
    (net (code "123") (name "Net-(U$4C-XOSC32M-Q1)") (class "Default")
      (node (ref "CC_CX1") (pin "1") (pinfunction "1_1") (pintype "passive"))
      (node (ref "U$4") (pin "13") (pinfunction "XOSC32M-Q1_13") (pintype "input"))
      (node (ref "X1") (pin "1") (pinfunction "1_1") (pintype "bidirectional"))
    )
    (net (code "124") (name "Net-(U$4C-XOSC32M-Q2)") (class "Default")
      (node (ref "CC_CX2") (pin "1") (pinfunction "1_1") (pintype "passive"))
      (node (ref "U$4") (pin "12") (pinfunction "XOSC32M-Q2_12") (pintype "output"))
      (node (ref "X1") (pin "3") (pinfunction "2_3") (pintype "bidirectional"))
    )
    (net (code "125") (name "Net-(U$12-P$1)") (class "Default")
      (node (ref "RT1") (pin "1") (pinfunction "1_1") (pintype "passive"))
      (node (ref "U$12") (pin "P1") (pinfunction "P$1_P1") (pintype "bidirectional"))
    )
    (net (code "126") (name "Net-(U$12-P$2)") (class "Default")
      (node (ref "RT2") (pin "1") (pinfunction "1_1") (pintype "passive"))
      (node (ref "U$12") (pin "P2") (pinfunction "P$2_P2") (pintype "bidirectional"))
    )
    (net (code "127") (name "Net-(U$12-P$3)") (class "Default")
      (node (ref "RT3") (pin "1") (pinfunction "1_1") (pintype "passive"))
      (node (ref "U$12") (pin "P3") (pinfunction "P$3_P3") (pintype "bidirectional"))
    )
    (net (code "128") (name "Net-(U$12-P$4)") (class "Default")
      (node (ref "U$10") (pin "IB") (pinfunction "IB_IB") (pintype "bidirectional"))
      (node (ref "U$11") (pin "IB") (pinfunction "IB_IB") (pintype "bidirectional"))
      (node (ref "U$12") (pin "P4") (pinfunction "P$4_P4") (pintype "bidirectional"))
      (node (ref "U$9") (pin "IB") (pinfunction "IB_IB") (pintype "bidirectional"))
    )
    (net (code "129") (name "Net-(U2-1V2O)") (class "Default")
      (node (ref "U2") (pin "22") (pinfunction "1V2O_22") (pintype "passive"))
      (node (ref "W5500-C4") (pin "1") (pinfunction "1_1") (pintype "passive"))
    )
    (net (code "130") (name "Net-(U2-EXRES1)") (class "Default")
      (node (ref "U2") (pin "10") (pinfunction "EXRES1_10") (pintype "passive"))
      (node (ref "W5500-R12") (pin "2") (pinfunction "2_2") (pintype "passive"))
    )
    (net (code "131") (name "Net-(U2-RSVD-Pad23)") (class "Default")
      (node (ref "U2") (pin "23") (pinfunction "RSVD_23") (pintype "passive"))
      (node (ref "W5500-R11") (pin "2") (pinfunction "2_2") (pintype "passive"))
    )
    (net (code "132") (name "Net-(U2-TOCAP)") (class "Default")
      (node (ref "U2") (pin "20") (pinfunction "TOCAP_20") (pintype "passive"))
      (node (ref "W5500-C3") (pin "1") (pinfunction "1_1") (pintype "passive"))
    )
    (net (code "133") (name "Net-(U2-XI{slash}CLKIN)") (class "Default")
      (node (ref "U2") (pin "30") (pinfunction "XI/CLKIN_30") (pintype "passive"))
      (node (ref "W5500-C1") (pin "1") (pinfunction "1_1") (pintype "passive"))
      (node (ref "W5500-R10") (pin "1") (pinfunction "1_1") (pintype "passive"))
      (node (ref "W5500-XTAL") (pin "1") (pinfunction "1_1") (pintype "passive"))
    )
    (net (code "134") (name "Net-(U2-XO)") (class "Default")
      (node (ref "U2") (pin "31") (pinfunction "XO_31") (pintype "passive"))
      (node (ref "W5500-C2") (pin "1") (pinfunction "1_1") (pintype "passive"))
      (node (ref "W5500-R10") (pin "2") (pinfunction "2_2") (pintype "passive"))
      (node (ref "W5500-XTAL") (pin "2") (pinfunction "2_2") (pintype "passive"))
    )
    (net (code "135") (name "Q1") (class "Default")
      (node (ref "IC2") (pin "15") (pinfunction "QA_15") (pintype "tri_state"))
      (node (ref "SR_OUT1") (pin "3") (pinfunction "3_3") (pintype "passive"))
    )
    (net (code "136") (name "Q2") (class "Default")
      (node (ref "IC2") (pin "1") (pinfunction "QB_1") (pintype "tri_state"))
      (node (ref "SR_OUT1") (pin "4") (pinfunction "4_4") (pintype "passive"))
    )
    (net (code "137") (name "Q3") (class "Default")
      (node (ref "IC2") (pin "2") (pinfunction "QC_2") (pintype "tri_state"))
      (node (ref "SR_OUT1") (pin "5") (pinfunction "5_5") (pintype "passive"))
    )
    (net (code "138") (name "Q4") (class "Default")
      (node (ref "IC2") (pin "3") (pinfunction "QD_3") (pintype "tri_state"))
      (node (ref "SR_OUT1") (pin "6") (pinfunction "6_6") (pintype "passive"))
    )
    (net (code "139") (name "Q5") (class "Default")
      (node (ref "IC2") (pin "4") (pinfunction "QE_4") (pintype "tri_state"))
      (node (ref "SR_OUT1") (pin "7") (pinfunction "7_7") (pintype "passive"))
    )
    (net (code "140") (name "Q6") (class "Default")
      (node (ref "IC2") (pin "5") (pinfunction "QF_5") (pintype "tri_state"))
      (node (ref "SR_OUT1") (pin "8") (pinfunction "8_8") (pintype "passive"))
    )
    (net (code "141") (name "Q7") (class "Default")
      (node (ref "IC2") (pin "6") (pinfunction "QG_6") (pintype "tri_state"))
      (node (ref "SR_OUT1") (pin "9") (pinfunction "9_9") (pintype "passive"))
    )
    (net (code "142") (name "Q8") (class "Default")
      (node (ref "IC2") (pin "7") (pinfunction "QH_7") (pintype "tri_state"))
      (node (ref "SR_OUT1") (pin "10") (pinfunction "10_10") (pintype "passive"))
    )
    (net (code "143") (name "Q9") (class "Default")
      (node (ref "IC3") (pin "15") (pinfunction "QA_15") (pintype "tri_state"))
      (node (ref "SR_OUT2") (pin "3") (pinfunction "3_3") (pintype "passive"))
    )
    (net (code "144") (name "Q10") (class "Default")
      (node (ref "IC3") (pin "1") (pinfunction "QB_1") (pintype "tri_state"))
      (node (ref "SR_OUT2") (pin "4") (pinfunction "4_4") (pintype "passive"))
    )
    (net (code "145") (name "Q11") (class "Default")
      (node (ref "IC3") (pin "2") (pinfunction "QC_2") (pintype "tri_state"))
      (node (ref "SR_OUT2") (pin "5") (pinfunction "5_5") (pintype "passive"))
    )
    (net (code "146") (name "Q12") (class "Default")
      (node (ref "IC3") (pin "3") (pinfunction "QD_3") (pintype "tri_state"))
      (node (ref "SR_OUT2") (pin "6") (pinfunction "6_6") (pintype "passive"))
    )
    (net (code "147") (name "Q13") (class "Default")
      (node (ref "IC3") (pin "4") (pinfunction "QE_4") (pintype "tri_state"))
      (node (ref "SR_OUT2") (pin "7") (pinfunction "7_7") (pintype "passive"))
    )
    (net (code "148") (name "Q14") (class "Default")
      (node (ref "IC3") (pin "5") (pinfunction "QF_5") (pintype "tri_state"))
      (node (ref "SR_OUT2") (pin "8") (pinfunction "8_8") (pintype "passive"))
    )
    (net (code "149") (name "Q15") (class "Default")
      (node (ref "IC3") (pin "6") (pinfunction "QG_6") (pintype "tri_state"))
      (node (ref "SR_OUT2") (pin "9") (pinfunction "9_9") (pintype "passive"))
    )
    (net (code "150") (name "Q16") (class "Default")
      (node (ref "IC3") (pin "7") (pinfunction "QH_7") (pintype "tri_state"))
      (node (ref "SR_OUT2") (pin "10") (pinfunction "10_10") (pintype "passive"))
    )
    (net (code "151") (name "QS") (class "Default")
      (node (ref "IC2") (pin "9") (pinfunction "QH*_9") (pintype "tri_state"))
      (node (ref "IC3") (pin "14") (pinfunction "SER_14") (pintype "input"))
    )
    (net (code "152") (name "QS2") (class "Default")
      (node (ref "IC3") (pin "9") (pinfunction "QH*_9") (pintype "tri_state"))
      (node (ref "IC5") (pin "14") (pinfunction "SER_14") (pintype "input"))
    )
    (net (code "153") (name "RXN") (class "Default")
      (node (ref "ETH-C4") (pin "2") (pinfunction "2_2") (pintype "passive"))
      (node (ref "ETH-R7") (pin "1") (pinfunction "1_1") (pintype "passive"))
      (node (ref "U2") (pin "5") (pinfunction "RXN_5") (pintype "passive"))
    )
    (net (code "154") (name "RXP") (class "Default")
      (node (ref "ETH-C2") (pin "2") (pinfunction "2_2") (pintype "passive"))
      (node (ref "ETH-R6") (pin "2") (pinfunction "2_2") (pintype "passive"))
      (node (ref "U2") (pin "6") (pinfunction "RXP_6") (pintype "passive"))
    )
    (net (code "155") (name "SD_CS") (class "Default")
      (node (ref "STM_CHIP") (pin "55") (pinfunction "PB3_55") (pintype "bidirectional"))
      (node (ref "U$13") (pin "SD_CS") (pinfunction "SD_CS_SD_CS") (pintype "bidirectional"))
    )
    (net (code "156") (name "SERIAL_RX") (class "Default")
      (node (ref "STM-USART") (pin "3") (pinfunction "3_3") (pintype "passive"))
      (node (ref "STM_CHIP") (pin "43") (pinfunction "PA10_43") (pintype "bidirectional"))
    )
    (net (code "157") (name "SERIAL_TX") (class "Default")
      (node (ref "STM-USART") (pin "2") (pinfunction "2_2") (pintype "passive"))
      (node (ref "STM_CHIP") (pin "42") (pinfunction "PA9_42") (pintype "bidirectional"))
    )
    (net (code "158") (name "SIM900_PWRKEY") (class "Default")
      (node (ref "IC1") (pin "P$1") (pinfunction "PWRKEY_P$1") (pintype "power_in"))
      (node (ref "SIM900-T3") (pin "C") (pinfunction "C_C") (pintype "passive"))
    )
    (net (code "159") (name "SIM900_RESET") (class "Default")
      (node (ref "IC1") (pin "P$16") (pinfunction "NRESET_P$16") (pintype "bidirectional"))
      (node (ref "SIM900-T4") (pin "C") (pinfunction "C_C") (pintype "passive"))
    )
    (net (code "160") (name "SIM_NETLIGHT") (class "Default")
      (node (ref "IC1") (pin "P$52") (pinfunction "NETLIGHT_P$52") (pintype "bidirectional"))
      (node (ref "SIM900-R8") (pin "2") (pinfunction "2_2") (pintype "passive"))
    )
    (net (code "161") (name "SIM_PWRKEY") (class "Default")
      (node (ref "SIM900-R10") (pin "1") (pinfunction "1_1") (pintype "passive"))
      (node (ref "STM_CHIP") (pin "41") (pinfunction "PA8_41") (pintype "bidirectional"))
    )
    (net (code "162") (name "SIM_RESET") (class "Default")
      (node (ref "SIM900-R11") (pin "1") (pinfunction "1_1") (pintype "passive"))
    )
    (net (code "163") (name "SIM_RX") (class "Default")
      (node (ref "IC1") (pin "P$10") (pinfunction "RXD_P$10") (pintype "input"))
      (node (ref "STM_CHIP") (pin "51") (pinfunction "PC10_51") (pintype "bidirectional"))
    )
    (net (code "164") (name "SIM_STATUS") (class "Default")
      (node (ref "IC1") (pin "P$66") (pinfunction "STATUS_P$66") (pintype "bidirectional"))
      (node (ref "SIM900-R5") (pin "2") (pinfunction "2_2") (pintype "passive"))
    )
    (net (code "165") (name "SIM_TX") (class "Default")
      (node (ref "IC1") (pin "P$9") (pinfunction "TXD_P$9") (pintype "output"))
      (node (ref "STM_CHIP") (pin "50") (pinfunction "PA15_50") (pintype "bidirectional"))
    )
    (net (code "166") (name "SR_DS") (class "Default")
      (node (ref "IC2") (pin "14") (pinfunction "SER_14") (pintype "input"))
      (node (ref "STM_CHIP") (pin "8") (pinfunction "PC0_8") (pintype "bidirectional"))
    )
    (net (code "167") (name "SR_RST") (class "Default")
      (node (ref "IC2") (pin "10") (pinfunction "SCL_10") (pintype "input"))
      (node (ref "IC3") (pin "10") (pinfunction "SCL_10") (pintype "input"))
      (node (ref "IC5") (pin "10") (pinfunction "SCL_10") (pintype "input"))
      (node (ref "STM_CHIP") (pin "11") (pinfunction "PC3_11") (pintype "bidirectional"))
    )
    (net (code "168") (name "SR_SHCP") (class "Default")
      (node (ref "IC2") (pin "11") (pinfunction "SCK_11") (pintype "input"))
      (node (ref "IC3") (pin "11") (pinfunction "SCK_11") (pintype "input"))
      (node (ref "IC5") (pin "11") (pinfunction "SCK_11") (pintype "input"))
      (node (ref "STM_CHIP") (pin "10") (pinfunction "PC2_10") (pintype "bidirectional"))
    )
    (net (code "169") (name "SR_STCP") (class "Default")
      (node (ref "IC2") (pin "12") (pinfunction "RCK_12") (pintype "input"))
      (node (ref "IC3") (pin "12") (pinfunction "RCK_12") (pintype "input"))
      (node (ref "IC5") (pin "12") (pinfunction "RCK_12") (pintype "input"))
      (node (ref "STM_CHIP") (pin "9") (pinfunction "PC1_9") (pintype "bidirectional"))
    )
    (net (code "170") (name "SWD_NRST") (class "Default")
      (node (ref "S1") (pin "1") (pinfunction "1_1") (pintype "passive"))
      (node (ref "S1") (pin "2") (pinfunction "2_2") (pintype "passive"))
      (node (ref "STM-C8") (pin "1") (pinfunction "1_1") (pintype "passive"))
      (node (ref "STM_CHIP") (pin "7") (pinfunction "NRST_7") (pintype "bidirectional"))
    )
    (net (code "171") (name "SWD_TCK") (class "Default")
      (node (ref "STM-SWD") (pin "2") (pinfunction "2_2") (pintype "passive"))
      (node (ref "STM_CHIP") (pin "49") (pinfunction "PA14_49") (pintype "bidirectional"))
    )
    (net (code "172") (name "SWD_TMS") (class "Default")
      (node (ref "STM-SWD") (pin "4") (pinfunction "4_4") (pintype "passive"))
      (node (ref "STM_CHIP") (pin "46") (pinfunction "PA13_46") (pintype "bidirectional"))
    )
    (net (code "173") (name "TXN") (class "Default")
      (node (ref "ETH-R2") (pin "1") (pinfunction "1_1") (pintype "passive"))
      (node (ref "ETHERNET") (pin "2") (pinfunction "TX-_2") (pintype "bidirectional"))
      (node (ref "U2") (pin "1") (pinfunction "TXN_1") (pintype "passive"))
    )
    (net (code "174") (name "TXP") (class "Default")
      (node (ref "ETH-R1") (pin "1") (pinfunction "1_1") (pintype "passive"))
      (node (ref "ETHERNET") (pin "1") (pinfunction "TX+_1") (pintype "bidirectional"))
      (node (ref "U2") (pin "2") (pinfunction "TXP_2") (pintype "passive"))
    )
    (net (code "175") (name "T_CLK") (class "Default")
      (node (ref "STM_CHIP") (pin "27") (pinfunction "PB1_27") (pintype "bidirectional"))
      (node (ref "U$13") (pin "T_CLK") (pinfunction "T_CLK_T_CLK") (pintype "bidirectional"))
    )
    (net (code "176") (name "T_DIN") (class "Default")
      (node (ref "STM_CHIP") (pin "29") (pinfunction "PB10_29") (pintype "bidirectional"))
      (node (ref "U$13") (pin "T_DIN") (pinfunction "T_DIN_T_DIN") (pintype "bidirectional"))
    )
    (net (code "177") (name "T_DO") (class "Default")
      (node (ref "STM_CHIP") (pin "30") (pinfunction "PB11_30") (pintype "bidirectional"))
      (node (ref "U$13") (pin "T_DO") (pinfunction "T_DO_T_DO") (pintype "bidirectional"))
    )
    (net (code "178") (name "T_IRQ") (class "Default")
      (node (ref "STM_CHIP") (pin "28") (pinfunction "PB2_28") (pintype "bidirectional"))
      (node (ref "U$13") (pin "T_IRQ") (pinfunction "T_IRQ_T_IRQ") (pintype "bidirectional"))
    )
    (net (code "179") (name "USB_DM") (class "Default")
      (node (ref "STM_CHIP") (pin "44") (pinfunction "PA11_44") (pintype "bidirectional"))
      (node (ref "USB_IN") (pin "D-1") (pinfunction "D-_D-1") (pintype "bidirectional"))
    )
    (net (code "180") (name "USB_DP") (class "Default")
      (node (ref "STM_CHIP") (pin "45") (pinfunction "PA12_45") (pintype "bidirectional"))
      (node (ref "USB_IN") (pin "D+1") (pinfunction "D+_D+1") (pintype "bidirectional"))
    )
    (net (code "181") (name "USIM_CLK") (class "Default")
      (node (ref "SIM900-R2") (pin "2") (pinfunction "2_2") (pintype "passive"))
      (node (ref "U$8") (pin "SIM_CLK") (pinfunction "SIM_CLK_SIM_CLK") (pintype "bidirectional"))
    )
    (net (code "182") (name "USIM_DATA") (class "Default")
      (node (ref "SIM900-R3") (pin "2") (pinfunction "2_2") (pintype "passive"))
      (node (ref "U$8") (pin "SIM_IO") (pinfunction "SIM_IO_SIM_IO") (pintype "bidirectional"))
    )
    (net (code "183") (name "USIM_RESET") (class "Default")
      (node (ref "SIM900-R1") (pin "2") (pinfunction "2_2") (pintype "passive"))
      (node (ref "U$8") (pin "SIM_RST") (pinfunction "SIM_RST_SIM_RST") (pintype "bidirectional"))
    )
    (net (code "184") (name "USIM_VCC") (class "Default")
      (node (ref "IC1") (pin "P$30") (pinfunction "SIM_VDD_P$30") (pintype "power_in"))
      (node (ref "SIM900-C4") (pin "1") (pinfunction "1_1") (pintype "passive"))
      (node (ref "SIM900-C5") (pin "1") (pinfunction "1_1") (pintype "passive"))
      (node (ref "SIM_C1") (pin "2") (pinfunction "2_2") (pintype "passive"))
      (node (ref "SIM_C2") (pin "2") (pinfunction "2_2") (pintype "passive"))
      (node (ref "U$8") (pin "SIM_VDD") (pinfunction "SIM_VDD_SIM_VDD") (pintype "bidirectional"))
    )
    (net (code "185") (name "VBAT") (class "Default")
      (node (ref "BAT1") (pin "PWR@1") (pinfunction "+_PWR@1") (pintype "power_in"))
      (node (ref "STM_CHIP") (pin "1") (pinfunction "VLCD_1") (pintype "power_in"))
    )
    (net (code "186") (name "VCC") (class "Default")
      (node (ref "ETH-R1") (pin "2") (pinfunction "2_2") (pintype "passive"))
      (node (ref "ETH-R2") (pin "2") (pinfunction "2_2") (pintype "passive"))
      (node (ref "ETH-R3") (pin "2") (pinfunction "2_2") (pintype "passive"))
      (node (ref "STM-C9") (pin "1") (pinfunction "1_1") (pintype "passive"))
      (node (ref "STM-L1") (pin "2") (pinfunction "2_2") (pintype "passive"))
      (node (ref "STM_CHIP") (pin "13") (pinfunction "VDDA_13") (pintype "power_in"))
      (node (ref "SYS-C4") (pin "1") (pinfunction "1_1") (pintype "passive"))
      (node (ref "SYS-R2") (pin "2") (pinfunction "2_2") (pintype "passive"))
      (node (ref "U2") (pin "11") (pinfunction "AVDD_11") (pintype "passive"))
      (node (ref "U2") (pin "15") (pinfunction "AVDD_15") (pintype "passive"))
      (node (ref "U2") (pin "17") (pinfunction "AVDD_17") (pintype "passive"))
      (node (ref "U2") (pin "21") (pinfunction "AVDD_21") (pintype "passive"))
      (node (ref "U2") (pin "4") (pinfunction "AVDD_4") (pintype "passive"))
      (node (ref "U2") (pin "8") (pinfunction "AVDD_8") (pintype "passive"))
      (node (ref "W5500-C10") (pin "1") (pinfunction "1_1") (pintype "passive"))
      (node (ref "W5500-C11") (pin "1") (pinfunction "1_1") (pintype "passive"))
      (node (ref "W5500-C12") (pin "+") (pinfunction "+_+") (pintype "passive"))
      (node (ref "W5500-C6") (pin "1") (pinfunction "1_1") (pintype "passive"))
      (node (ref "W5500-C7") (pin "1") (pinfunction "1_1") (pintype "passive"))
      (node (ref "W5500-C8") (pin "1") (pinfunction "1_1") (pintype "passive"))
      (node (ref "W5500-C9") (pin "1") (pinfunction "1_1") (pintype "passive"))
    )
    (net (code "187") (name "VDD") (class "Default")
      (node (ref "CC_C14") (pin "1") (pinfunction "1_1") (pintype "passive"))
      (node (ref "CC_C20") (pin "1") (pinfunction "1_1") (pintype "passive"))
      (node (ref "CC_C8") (pin "1") (pinfunction "1_1") (pintype "passive"))
      (node (ref "DHT-R1") (pin "1") (pinfunction "1_1") (pintype "passive"))
      (node (ref "ESP_EXT") (pin "1") (pinfunction "1_1") (pintype "passive"))
      (node (ref "ETHERNET") (pin "12") (pinfunction "LED2_A_12") (pintype "bidirectional"))
      (node (ref "ETHERNET") (pin "9") (pinfunction "LED1_A_9") (pintype "bidirectional"))
      (node (ref "IC2") (pin "16") (pinfunction "VCC_16") (pintype "power_in"))
      (node (ref "IC3") (pin "16") (pinfunction "VCC_16") (pintype "power_in"))
      (node (ref "IC5") (pin "16") (pinfunction "VCC_16") (pintype "power_in"))
      (node (ref "LCD-R1") (pin "2") (pinfunction "2_2") (pintype "passive"))
      (node (ref "PWR-SWT") (pin "1") (pinfunction "1_1") (pintype "passive"))
      (node (ref "RW5500-1") (pin "2") (pinfunction "1_2") (pintype "passive"))
      (node (ref "RW5500-1") (pin "3") (pinfunction "1_3") (pintype "passive"))
      (node (ref "RW5500-1") (pin "4") (pinfunction "1_4") (pintype "passive"))
      (node (ref "RW5500-3") (pin "1") (pinfunction "1_1") (pintype "passive"))
      (node (ref "R_VREG") (pin "2") (pinfunction "2_2") (pintype "passive"))
      (node (ref "SENSOR-DHT") (pin "1") (pinfunction "1_1") (pintype "passive"))
      (node (ref "SIM900-R4") (pin "2") (pinfunction "2_2") (pintype "passive"))
      (node (ref "SIM900-R7") (pin "2") (pinfunction "2_2") (pintype "passive"))
      (node (ref "STM-C1") (pin "2") (pinfunction "2_2") (pintype "passive"))
      (node (ref "STM-C10") (pin "1") (pinfunction "1_1") (pintype "passive"))
      (node (ref "STM-C11") (pin "1") (pinfunction "1_1") (pintype "passive"))
      (node (ref "STM-C12") (pin "1") (pinfunction "1_1") (pintype "passive"))
      (node (ref "STM-C13") (pin "1") (pinfunction "1_1") (pintype "passive"))
      (node (ref "STM-L1") (pin "1") (pinfunction "1_1") (pintype "passive"))
      (node (ref "STM-SWD") (pin "1") (pinfunction "1_1") (pintype "passive"))
      (node (ref "STM-USART") (pin "1") (pinfunction "1_1") (pintype "passive"))
      (node (ref "STM_CHIP") (pin "19") (pinfunction "VDD_4_19") (pintype "power_in"))
      (node (ref "STM_CHIP") (pin "32") (pinfunction "VDD_1_32") (pintype "power_in"))
      (node (ref "STM_CHIP") (pin "48") (pinfunction "VDD_2_48") (pintype "power_in"))
      (node (ref "STM_CHIP") (pin "64") (pinfunction "VDD_3_64") (pintype "power_in"))
      (node (ref "SYS-C3") (pin "1") (pinfunction "1_1") (pintype "passive"))
      (node (ref "SYS-L2") (pin "2") (pinfunction "2_2") (pintype "passive"))
      (node (ref "SYS-R2") (pin "1") (pinfunction "1_1") (pintype "passive"))
      (node (ref "U$13") (pin "LCD_VCC") (pinfunction "LCD_VCC_LCD_VCC") (pintype "power_in"))
      (node (ref "U$4") (pin "11") (pinfunction "AVDD_11") (pintype "power_in"))
      (node (ref "U$4") (pin "14") (pinfunction "AVDD_14") (pintype "power_in"))
      (node (ref "U$4") (pin "16") (pinfunction "AVDD_16") (pintype "power_in"))
      (node (ref "U$4") (pin "20") (pinfunction "AVDD_20") (pintype "power_in"))
      (node (ref "U$4") (pin "22") (pinfunction "AVDD_22") (pintype "power_in"))
      (node (ref "U$4") (pin "24") (pinfunction "AVDD-GUARD_24") (pintype "power_in"))
      (node (ref "U$4") (pin "8") (pinfunction "DVDD_8") (pintype "power_in"))
      (node (ref "U2") (pin "28") (pinfunction "VDD_28") (pintype "passive"))
      (node (ref "W5500-C13") (pin "+") (pinfunction "+_+") (pintype "passive"))
      (node (ref "W5500-C5") (pin "1") (pinfunction "1_1") (pintype "passive"))
      (node (ref "W5500-R13") (pin "2") (pinfunction "2_2") (pintype "passive"))
    )
    (net (code "188") (name "VESP") (class "Default")
      (node (ref "ESP-C1") (pin "1") (pinfunction "1_1") (pintype "passive"))
      (node (ref "ESP-GPIO0") (pin "1") (pinfunction "1_1") (pintype "passive"))
      (node (ref "ESP_EXT") (pin "2") (pinfunction "2_2") (pintype "passive"))
      (node (ref "U$5") (pin "CH_PD") (pinfunction "CH_PD_CH_PD") (pintype "bidirectional"))
      (node (ref "U$5") (pin "GPIO02") (pinfunction "GPIO2_GPIO02") (pintype "bidirectional"))
      (node (ref "U$5") (pin "REST") (pinfunction "REST_REST") (pintype "bidirectional"))
      (node (ref "U$5") (pin "VCC") (pinfunction "VCC_VCC") (pintype "power_in"))
    )
    (net (code "189") (name "unconnected-(IC1-ADC-PadP$25)") (class "Default")
      (node (ref "IC1") (pin "P$25") (pinfunction "ADC_P$25") (pintype "bidirectional"))
    )
    (net (code "190") (name "unconnected-(IC1-CTS-PadP$7)") (class "Default")
      (node (ref "IC1") (pin "P$7") (pinfunction "CTS_P$7") (pintype "output"))
    )
    (net (code "191") (name "unconnected-(IC1-DBG_RXD-PadP$28)") (class "Default")
      (node (ref "IC1") (pin "P$28") (pinfunction "DBG_RXD_P$28") (pintype "input"))
    )
    (net (code "192") (name "unconnected-(IC1-DBG_TXD-PadP$27)") (class "Default")
      (node (ref "IC1") (pin "P$27") (pinfunction "DBG_TXD_P$27") (pintype "output"))
    )
    (net (code "193") (name "unconnected-(IC1-DCD-PadP$5)") (class "Default")
      (node (ref "IC1") (pin "P$5") (pinfunction "DCD_P$5") (pintype "output"))
    )
    (net (code "194") (name "unconnected-(IC1-DISP_CLK-PadP$11)") (class "Default")
      (node (ref "IC1") (pin "P$11") (pinfunction "DISP_CLK_P$11") (pintype "bidirectional"))
    )
    (net (code "195") (name "unconnected-(IC1-DISP_CS-PadP$14)") (class "Default")
      (node (ref "IC1") (pin "P$14") (pinfunction "DISP_CS_P$14") (pintype "bidirectional"))
    )
    (net (code "196") (name "unconnected-(IC1-DISP_DATA-PadP$12)") (class "Default")
      (node (ref "IC1") (pin "P$12") (pinfunction "DISP_DATA_P$12") (pintype "bidirectional"))
    )
    (net (code "197") (name "unconnected-(IC1-DISP_DC-PadP$13)") (class "Default")
      (node (ref "IC1") (pin "P$13") (pinfunction "DISP_DC_P$13") (pintype "bidirectional"))
    )
    (net (code "198") (name "unconnected-(IC1-DTR-PadP$3)") (class "Default")
      (node (ref "IC1") (pin "P$3") (pinfunction "DTR_P$3") (pintype "input"))
    )
    (net (code "199") (name "unconnected-(IC1-GPIO1{slash}KBR4-PadP$40)") (class "Default")
      (node (ref "IC1") (pin "P$40") (pinfunction "GPIO1/KBR4_P$40") (pintype "bidirectional"))
    )
    (net (code "200") (name "unconnected-(IC1-GPIO2{slash}KBR3-PadP$41)") (class "Default")
      (node (ref "IC1") (pin "P$41") (pinfunction "GPIO2/KBR3_P$41") (pintype "bidirectional"))
    )
    (net (code "201") (name "unconnected-(IC1-GPIO3{slash}KBR2-PadP$42)") (class "Default")
      (node (ref "IC1") (pin "P$42") (pinfunction "GPIO3/KBR2_P$42") (pintype "bidirectional"))
    )
    (net (code "202") (name "unconnected-(IC1-GPIO4{slash}KBR1-PadP$43)") (class "Default")
      (node (ref "IC1") (pin "P$43") (pinfunction "GPIO4/KBR1_P$43") (pintype "bidirectional"))
    )
    (net (code "203") (name "unconnected-(IC1-GPIO5{slash}KBR0-PadP$44)") (class "Default")
      (node (ref "IC1") (pin "P$44") (pinfunction "GPIO5/KBR0_P$44") (pintype "bidirectional"))
    )
    (net (code "204") (name "unconnected-(IC1-GPIO6{slash}KBC4-PadP$47)") (class "Default")
      (node (ref "IC1") (pin "P$47") (pinfunction "GPIO6/KBC4_P$47") (pintype "bidirectional"))
    )
    (net (code "205") (name "unconnected-(IC1-GPIO7{slash}KBC3-PadP$48)") (class "Default")
      (node (ref "IC1") (pin "P$48") (pinfunction "GPIO7/KBC3_P$48") (pintype "bidirectional"))
    )
    (net (code "206") (name "unconnected-(IC1-GPIO8{slash}KBC2-PadP$49)") (class "Default")
      (node (ref "IC1") (pin "P$49") (pinfunction "GPIO8/KBC2_P$49") (pintype "bidirectional"))
    )
    (net (code "207") (name "unconnected-(IC1-GPIO9{slash}KBC1-PadP$50)") (class "Default")
      (node (ref "IC1") (pin "P$50") (pinfunction "GPIO9/KBC1_P$50") (pintype "bidirectional"))
    )
    (net (code "208") (name "unconnected-(IC1-GPIO10-PadP$51)") (class "Default")
      (node (ref "IC1") (pin "P$51") (pinfunction "GPIO10_P$51") (pintype "bidirectional"))
    )
    (net (code "209") (name "unconnected-(IC1-LINEIN_L-PadP$24)") (class "Default")
      (node (ref "IC1") (pin "P$24") (pinfunction "LINEIN_L_P$24") (pintype "bidirectional"))
    )
    (net (code "210") (name "unconnected-(IC1-LINEIN_R-PadP$23)") (class "Default")
      (node (ref "IC1") (pin "P$23") (pinfunction "LINEIN_R_P$23") (pintype "bidirectional"))
    )
    (net (code "211") (name "unconnected-(IC1-MIC_N-PadP$20)") (class "Default")
      (node (ref "IC1") (pin "P$20") (pinfunction "MIC_N_P$20") (pintype "bidirectional"))
    )
    (net (code "212") (name "unconnected-(IC1-MIC_P-PadP$19)") (class "Default")
      (node (ref "IC1") (pin "P$19") (pinfunction "MIC_P_P$19") (pintype "bidirectional"))
    )
    (net (code "213") (name "unconnected-(IC1-NC-PadP$2)") (class "Default")
      (node (ref "IC1") (pin "P$2") (pinfunction "NC_P$2") (pintype "no_connect"))
    )
    (net (code "214") (name "unconnected-(IC1-NC-PadP$6)") (class "Default")
      (node (ref "IC1") (pin "P$6") (pinfunction "NC_P$6") (pintype "no_connect"))
    )
    (net (code "215") (name "unconnected-(IC1-PWM1-PadP$35)") (class "Default")
      (node (ref "IC1") (pin "P$35") (pinfunction "PWM1_P$35") (pintype "bidirectional"))
    )
    (net (code "216") (name "unconnected-(IC1-PWM2-PadP$36)") (class "Default")
      (node (ref "IC1") (pin "P$36") (pinfunction "PWM2_P$36") (pintype "bidirectional"))
    )
    (net (code "217") (name "unconnected-(IC1-RI-PadP$4)") (class "Default")
      (node (ref "IC1") (pin "P$4") (pinfunction "RI_P$4") (pintype "output"))
    )
    (net (code "218") (name "unconnected-(IC1-RTS-PadP$8)") (class "Default")
      (node (ref "IC1") (pin "P$8") (pinfunction "RTS_P$8") (pintype "input"))
    )
    (net (code "219") (name "unconnected-(IC1-SCL-PadP$38)") (class "Default")
      (node (ref "IC1") (pin "P$38") (pinfunction "SCL_P$38") (pintype "bidirectional"))
    )
    (net (code "220") (name "unconnected-(IC1-SDA-PadP$37)") (class "Default")
      (node (ref "IC1") (pin "P$37") (pinfunction "SDA_P$37") (pintype "bidirectional"))
    )
    (net (code "221") (name "unconnected-(IC1-SIM_PRESENCE-PadP$34)") (class "Default")
      (node (ref "IC1") (pin "P$34") (pinfunction "SIM_PRESENCE_P$34") (pintype "bidirectional"))
    )
    (net (code "222") (name "unconnected-(IC1-SPK_N-PadP$22)") (class "Default")
      (node (ref "IC1") (pin "P$22") (pinfunction "SPK_N_P$22") (pintype "bidirectional"))
    )
    (net (code "223") (name "unconnected-(IC1-SPK_P-PadP$21)") (class "Default")
      (node (ref "IC1") (pin "P$21") (pinfunction "SPK_P_P$21") (pintype "bidirectional"))
    )
    (net (code "224") (name "unconnected-(IC1-VDD_EXT-PadP$15)") (class "Default")
      (node (ref "IC1") (pin "P$15") (pinfunction "VDD_EXT_P$15") (pintype "bidirectional"))
    )
    (net (code "225") (name "unconnected-(IC5A-QE-Pad4)") (class "Default")
      (node (ref "IC5") (pin "4") (pinfunction "QE_4") (pintype "tri_state"))
    )
    (net (code "226") (name "unconnected-(IC5A-QF-Pad5)") (class "Default")
      (node (ref "IC5") (pin "5") (pinfunction "QF_5") (pintype "tri_state"))
    )
    (net (code "227") (name "unconnected-(IC5A-QG-Pad6)") (class "Default")
      (node (ref "IC5") (pin "6") (pinfunction "QG_6") (pintype "tri_state"))
    )
    (net (code "228") (name "unconnected-(IC5A-QH*-Pad9)") (class "Default")
      (node (ref "IC5") (pin "9") (pinfunction "QH*_9") (pintype "tri_state"))
    )
    (net (code "229") (name "unconnected-(IC5A-QH-Pad7)") (class "Default")
      (node (ref "IC5") (pin "7") (pinfunction "QH_7") (pintype "tri_state"))
    )
    (net (code "230") (name "unconnected-(SENSOR-DHT-Pad3)") (class "Default")
      (node (ref "SENSOR-DHT") (pin "3") (pinfunction "3_3") (pintype "passive"))
    )
    (net (code "231") (name "unconnected-(STM_CHIP-BOOT0-Pad60)") (class "Default")
      (node (ref "STM_CHIP") (pin "60") (pinfunction "BOOT0_60") (pintype "input"))
    )
    (net (code "232") (name "unconnected-(STM_CHIP-PH0_-OSC_IN-Pad5)") (class "Default")
      (node (ref "STM_CHIP") (pin "5") (pinfunction "PH0_-OSC_IN_5") (pintype "bidirectional"))
    )
    (net (code "233") (name "unconnected-(U$5-GPIO4-PadGPIO04)") (class "Default")
      (node (ref "U$5") (pin "GPIO04") (pinfunction "GPIO4_GPIO04") (pintype "bidirectional"))
    )
    (net (code "234") (name "unconnected-(U$5-GPIO5-PadGPIO05)") (class "Default")
      (node (ref "U$5") (pin "GPIO05") (pinfunction "GPIO5_GPIO05") (pintype "bidirectional"))
    )
    (net (code "235") (name "unconnected-(U$5-PadADC)") (class "Default")
      (node (ref "U$5") (pin "ADC") (pinfunction "ADC_ADC") (pintype "bidirectional"))
    )
    (net (code "236") (name "unconnected-(U$5-PadGPIO12)") (class "Default")
      (node (ref "U$5") (pin "GPIO12") (pinfunction "GPIO12_GPIO12") (pintype "bidirectional"))
    )
    (net (code "237") (name "unconnected-(U$5-PadGPIO13)") (class "Default")
      (node (ref "U$5") (pin "GPIO13") (pinfunction "GPIO13_GPIO13") (pintype "bidirectional"))
    )
    (net (code "238") (name "unconnected-(U$5-PadGPIO14)") (class "Default")
      (node (ref "U$5") (pin "GPIO14") (pinfunction "GPIO14_GPIO14") (pintype "bidirectional"))
    )
    (net (code "239") (name "unconnected-(U$5-PadGPIO16)") (class "Default")
      (node (ref "U$5") (pin "GPIO16") (pinfunction "GPIO16_GPIO16") (pintype "bidirectional"))
    )
    (net (code "240") (name "unconnected-(U$8-PadVPP)") (class "Default")
      (node (ref "U$8") (pin "VPP") (pinfunction "VPP_VPP") (pintype "bidirectional"))
    )
    (net (code "241") (name "unconnected-(U2-DNC-Pad7)") (class "Default")
      (node (ref "U2") (pin "7") (pinfunction "DNC_7") (pintype "passive"))
    )
    (net (code "242") (name "unconnected-(U2-DUPLED-Pad26)") (class "Default")
      (node (ref "U2") (pin "26") (pinfunction "DUPLED_26") (pintype "passive"))
    )
    (net (code "243") (name "unconnected-(U2-INT_N-Pad36)") (class "Default")
      (node (ref "U2") (pin "36") (pinfunction "INT_N_36") (pintype "passive"))
    )
    (net (code "244") (name "unconnected-(U2-NC-Pad12)") (class "Default")
      (node (ref "U2") (pin "12") (pinfunction "NC_12") (pintype "passive"))
    )
    (net (code "245") (name "unconnected-(U2-NC-Pad13)") (class "Default")
      (node (ref "U2") (pin "13") (pinfunction "NC_13") (pintype "passive"))
    )
    (net (code "246") (name "unconnected-(U2-NC-Pad46)") (class "Default")
      (node (ref "U2") (pin "46") (pinfunction "NC_46") (pintype "passive"))
    )
    (net (code "247") (name "unconnected-(U2-NC-Pad47)") (class "Default")
      (node (ref "U2") (pin "47") (pinfunction "NC_47") (pintype "passive"))
    )
    (net (code "248") (name "unconnected-(U2-SPDLED-Pad24)") (class "Default")
      (node (ref "U2") (pin "24") (pinfunction "SPDLED_24") (pintype "passive"))
    )
    (net (code "249") (name "unconnected-(U2-VBG-Pad18)") (class "Default")
      (node (ref "U2") (pin "18") (pinfunction "VBG_18") (pintype "passive"))
    )
    (net (code "250") (name "unconnected-(USB_IN-ID-PadID1)") (class "Default")
      (node (ref "USB_IN") (pin "ID1") (pinfunction "ID_ID1") (pintype "bidirectional"))
    )
  )
)
